# Target_Control_System.net
KiCad netlist of a schematic drawn in Altium Designer
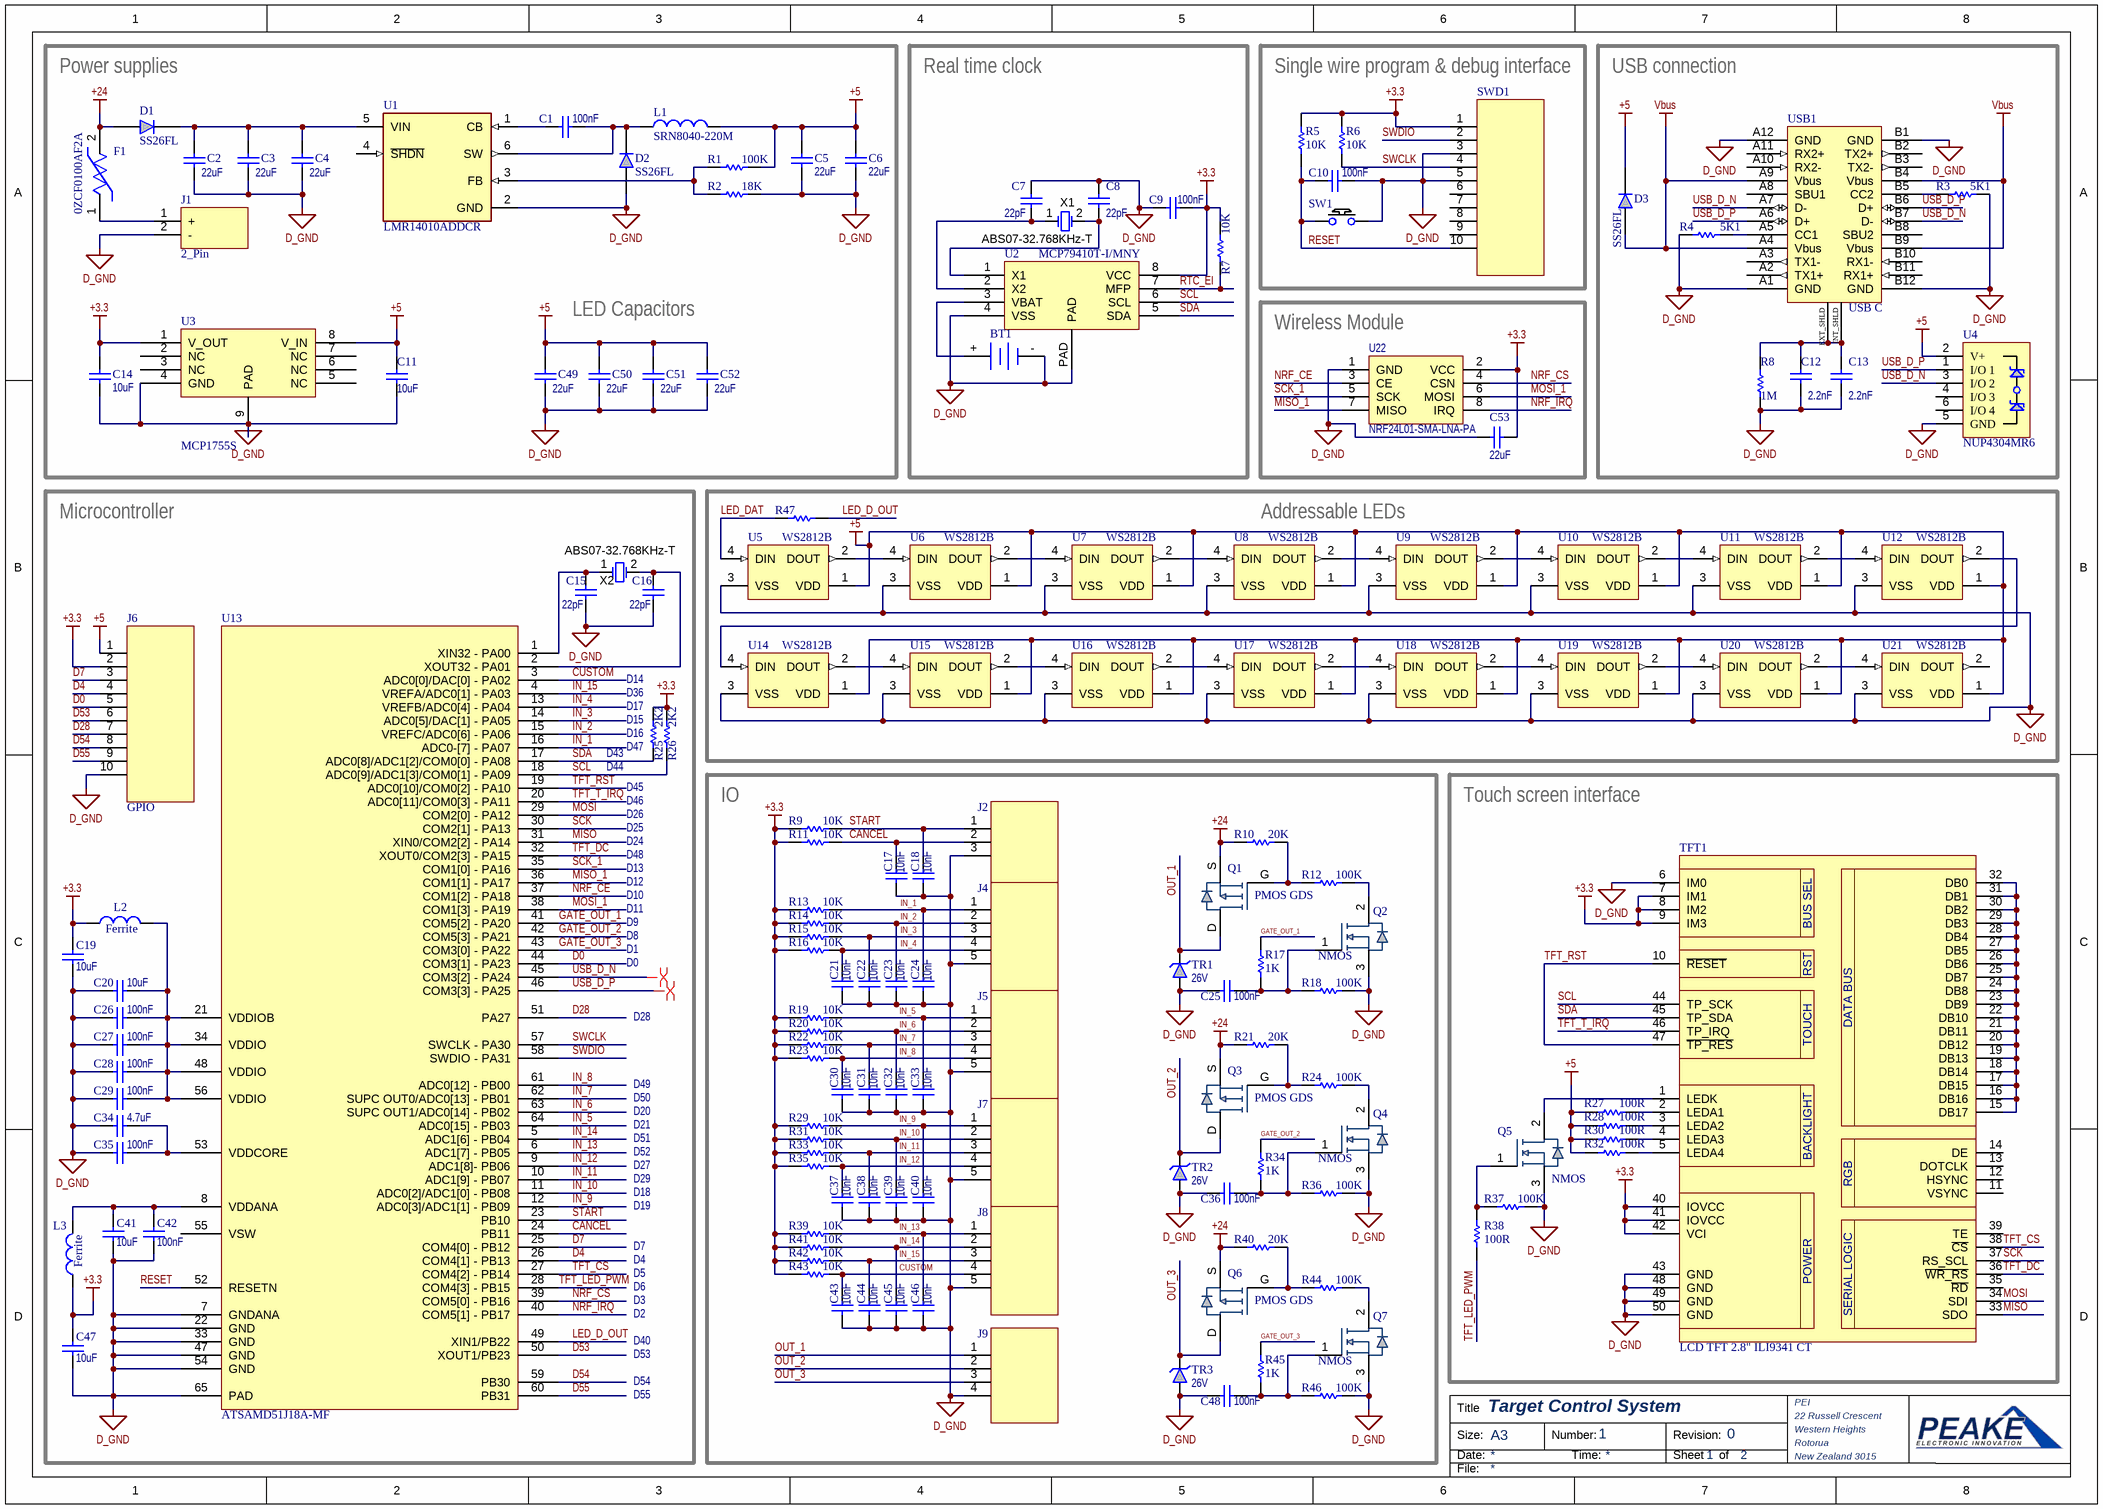
[diagram p0: Target Control System.SchDoc]

(export (version "E")
  (design (tool "Eeschema 10.0.6"))
  (components
    (comp (ref "BT1")
      (value "CR2032 Batt Holder")
      (footprint "CR2032 Batt Holder-Footprint-1")
      (description "SMD CR2032 coin cell holder")
      (libsource (lib "Scion Research") (part "CMP-00042-2"))
    )
    (comp (ref "C1")
      (value "100nF")
      (footprint "0603_CAP")
      (description "SMD Capacitor")
      (fields (field (name "Comment") "Capacitor"))
      (libsource (lib "Scion Research") (part "CMP-019-00005-2"))
    )
    (comp (ref "C2")
      (value "22uF")
      (footprint "0805_CAP")
      (description "SMD Capacitor")
      (fields (field (name "Comment") "Capacitor"))
      (libsource (lib "Scion Research") (part "CMP-019-00005-2"))
    )
    (comp (ref "C3")
      (value "22uF")
      (footprint "0805_CAP")
      (description "SMD Capacitor")
      (fields (field (name "Comment") "Capacitor"))
      (libsource (lib "Scion Research") (part "CMP-019-00005-2"))
    )
    (comp (ref "C4")
      (value "22uF")
      (footprint "0805_CAP")
      (description "SMD Capacitor")
      (fields (field (name "Comment") "Capacitor"))
      (libsource (lib "Scion Research") (part "CMP-019-00005-2"))
    )
    (comp (ref "C5")
      (value "22uF")
      (footprint "0805_CAP")
      (description "SMD Capacitor")
      (fields (field (name "Comment") "Capacitor"))
      (libsource (lib "Scion Research") (part "CMP-019-00005-2"))
    )
    (comp (ref "C6")
      (value "22uF")
      (footprint "0805_CAP")
      (description "SMD Capacitor")
      (fields (field (name "Comment") "Capacitor"))
      (libsource (lib "Scion Research") (part "CMP-019-00005-2"))
    )
    (comp (ref "C7")
      (value "22pF")
      (footprint "0603_CAP")
      (description "SMD Capacitor")
      (fields (field (name "Comment") "Capacitor"))
      (libsource (lib "Scion Research") (part "CMP-019-00005-2"))
    )
    (comp (ref "C8")
      (value "22pF")
      (footprint "0603_CAP")
      (description "SMD Capacitor")
      (fields (field (name "Comment") "Capacitor"))
      (libsource (lib "Scion Research") (part "CMP-019-00005-2"))
    )
    (comp (ref "C9")
      (value "100nF")
      (footprint "0603_CAP")
      (description "SMD Capacitor")
      (fields (field (name "Comment") "Capacitor"))
      (libsource (lib "Scion Research") (part "CMP-019-00005-2"))
    )
    (comp (ref "C10")
      (value "100nF")
      (footprint "0603_CAP")
      (description "SMD Capacitor")
      (fields (field (name "Comment") "Capacitor"))
      (libsource (lib "Scion Research") (part "CMP-019-00005-2"))
    )
    (comp (ref "C11")
      (value "10uF")
      (footprint "0603_CAP")
      (description "SMD Capacitor")
      (fields (field (name "Comment") "Capacitor"))
      (libsource (lib "Scion Research") (part "CMP-019-00005-2"))
    )
    (comp (ref "C12")
      (value "2.2nF")
      (footprint "0603_CAP")
      (description "SMD Capacitor")
      (fields (field (name "Comment") "Capacitor"))
      (libsource (lib "Scion Research") (part "CMP-019-00005-2"))
    )
    (comp (ref "C13")
      (value "2.2nF")
      (footprint "0603_CAP")
      (description "SMD Capacitor")
      (fields (field (name "Comment") "Capacitor"))
      (libsource (lib "Scion Research") (part "CMP-019-00005-2"))
    )
    (comp (ref "C14")
      (value "10uF")
      (footprint "0603_CAP")
      (description "SMD Capacitor")
      (fields (field (name "Comment") "Capacitor"))
      (libsource (lib "Scion Research") (part "CMP-019-00005-2"))
    )
    (comp (ref "C15")
      (value "22pF")
      (footprint "0603_CAP")
      (description "SMD Capacitor")
      (fields (field (name "Comment") "Capacitor"))
      (libsource (lib "Scion Research") (part "CMP-019-00005-2"))
    )
    (comp (ref "C16")
      (value "22pF")
      (footprint "0603_CAP")
      (description "SMD Capacitor")
      (fields (field (name "Comment") "Capacitor"))
      (libsource (lib "Scion Research") (part "CMP-019-00005-2"))
    )
    (comp (ref "C17")
      (value "10nF")
      (footprint "0603_CAP")
      (description "SMD Capacitor")
      (fields (field (name "Comment") "Capacitor"))
      (libsource (lib "Scion Research") (part "CMP-019-00005-2"))
    )
    (comp (ref "C18")
      (value "10nF")
      (footprint "0603_CAP")
      (description "SMD Capacitor")
      (fields (field (name "Comment") "Capacitor"))
      (libsource (lib "Scion Research") (part "CMP-019-00005-2"))
    )
    (comp (ref "C19")
      (value "10uF")
      (footprint "0603_CAP")
      (description "SMD Capacitor")
      (fields (field (name "Comment") "Capacitor"))
      (libsource (lib "Scion Research") (part "CMP-019-00005-2"))
    )
    (comp (ref "C20")
      (value "10uF")
      (footprint "0603_CAP")
      (description "SMD Capacitor")
      (fields (field (name "Comment") "Capacitor"))
      (libsource (lib "Scion Research") (part "CMP-019-00005-2"))
    )
    (comp (ref "C21")
      (value "10nF")
      (footprint "0603_CAP")
      (description "SMD Capacitor")
      (fields (field (name "Comment") "Capacitor"))
      (libsource (lib "Scion Research") (part "CMP-019-00005-2"))
    )
    (comp (ref "C22")
      (value "10nF")
      (footprint "0603_CAP")
      (description "SMD Capacitor")
      (fields (field (name "Comment") "Capacitor"))
      (libsource (lib "Scion Research") (part "CMP-019-00005-2"))
    )
    (comp (ref "C23")
      (value "10nF")
      (footprint "0603_CAP")
      (description "SMD Capacitor")
      (fields (field (name "Comment") "Capacitor"))
      (libsource (lib "Scion Research") (part "CMP-019-00005-2"))
    )
    (comp (ref "C24")
      (value "10nF")
      (footprint "0603_CAP")
      (description "SMD Capacitor")
      (fields (field (name "Comment") "Capacitor"))
      (libsource (lib "Scion Research") (part "CMP-019-00005-2"))
    )
    (comp (ref "C25")
      (value "100nF")
      (footprint "0603_CAP")
      (description "SMD Capacitor")
      (fields (field (name "Comment") "Capacitor"))
      (libsource (lib "Scion Research") (part "CMP-019-00005-2"))
    )
    (comp (ref "C26")
      (value "100nF")
      (footprint "0603_CAP")
      (description "SMD Capacitor")
      (fields (field (name "Comment") "Capacitor"))
      (libsource (lib "Scion Research") (part "CMP-019-00005-2"))
    )
    (comp (ref "C27")
      (value "100nF")
      (footprint "0603_CAP")
      (description "SMD Capacitor")
      (fields (field (name "Comment") "Capacitor"))
      (libsource (lib "Scion Research") (part "CMP-019-00005-2"))
    )
    (comp (ref "C28")
      (value "100nF")
      (footprint "0603_CAP")
      (description "SMD Capacitor")
      (fields (field (name "Comment") "Capacitor"))
      (libsource (lib "Scion Research") (part "CMP-019-00005-2"))
    )
    (comp (ref "C29")
      (value "100nF")
      (footprint "0603_CAP")
      (description "SMD Capacitor")
      (fields (field (name "Comment") "Capacitor"))
      (libsource (lib "Scion Research") (part "CMP-019-00005-2"))
    )
    (comp (ref "C30")
      (value "10nF")
      (footprint "0603_CAP")
      (description "SMD Capacitor")
      (fields (field (name "Comment") "Capacitor"))
      (libsource (lib "Scion Research") (part "CMP-019-00005-2"))
    )
    (comp (ref "C31")
      (value "10nF")
      (footprint "0603_CAP")
      (description "SMD Capacitor")
      (fields (field (name "Comment") "Capacitor"))
      (libsource (lib "Scion Research") (part "CMP-019-00005-2"))
    )
    (comp (ref "C32")
      (value "10nF")
      (footprint "0603_CAP")
      (description "SMD Capacitor")
      (fields (field (name "Comment") "Capacitor"))
      (libsource (lib "Scion Research") (part "CMP-019-00005-2"))
    )
    (comp (ref "C33")
      (value "10nF")
      (footprint "0603_CAP")
      (description "SMD Capacitor")
      (fields (field (name "Comment") "Capacitor"))
      (libsource (lib "Scion Research") (part "CMP-019-00005-2"))
    )
    (comp (ref "C34")
      (value "4.7uF")
      (footprint "0603_CAP")
      (description "SMD Capacitor")
      (fields (field (name "Comment") "Capacitor"))
      (libsource (lib "Scion Research") (part "CMP-019-00005-2"))
    )
    (comp (ref "C35")
      (value "100nF")
      (footprint "0603_CAP")
      (description "SMD Capacitor")
      (fields (field (name "Comment") "Capacitor"))
      (libsource (lib "Scion Research") (part "CMP-019-00005-2"))
    )
    (comp (ref "C36")
      (value "100nF")
      (footprint "0603_CAP")
      (description "SMD Capacitor")
      (fields (field (name "Comment") "Capacitor"))
      (libsource (lib "Scion Research") (part "CMP-019-00005-2"))
    )
    (comp (ref "C37")
      (value "10nF")
      (footprint "0603_CAP")
      (description "SMD Capacitor")
      (fields (field (name "Comment") "Capacitor"))
      (libsource (lib "Scion Research") (part "CMP-019-00005-2"))
    )
    (comp (ref "C38")
      (value "10nF")
      (footprint "0603_CAP")
      (description "SMD Capacitor")
      (fields (field (name "Comment") "Capacitor"))
      (libsource (lib "Scion Research") (part "CMP-019-00005-2"))
    )
    (comp (ref "C39")
      (value "10nF")
      (footprint "0603_CAP")
      (description "SMD Capacitor")
      (fields (field (name "Comment") "Capacitor"))
      (libsource (lib "Scion Research") (part "CMP-019-00005-2"))
    )
    (comp (ref "C40")
      (value "10nF")
      (footprint "0603_CAP")
      (description "SMD Capacitor")
      (fields (field (name "Comment") "Capacitor"))
      (libsource (lib "Scion Research") (part "CMP-019-00005-2"))
    )
    (comp (ref "C41")
      (value "10uF")
      (footprint "0603_CAP")
      (description "SMD Capacitor")
      (fields (field (name "Comment") "Capacitor"))
      (libsource (lib "Scion Research") (part "CMP-019-00005-2"))
    )
    (comp (ref "C42")
      (value "100nF")
      (footprint "0603_CAP")
      (description "SMD Capacitor")
      (fields (field (name "Comment") "Capacitor"))
      (libsource (lib "Scion Research") (part "CMP-019-00005-2"))
    )
    (comp (ref "C43")
      (value "10nF")
      (footprint "0603_CAP")
      (description "SMD Capacitor")
      (fields (field (name "Comment") "Capacitor"))
      (libsource (lib "Scion Research") (part "CMP-019-00005-2"))
    )
    (comp (ref "C44")
      (value "10nF")
      (footprint "0603_CAP")
      (description "SMD Capacitor")
      (fields (field (name "Comment") "Capacitor"))
      (libsource (lib "Scion Research") (part "CMP-019-00005-2"))
    )
    (comp (ref "C45")
      (value "10nF")
      (footprint "0603_CAP")
      (description "SMD Capacitor")
      (fields (field (name "Comment") "Capacitor"))
      (libsource (lib "Scion Research") (part "CMP-019-00005-2"))
    )
    (comp (ref "C46")
      (value "10nF")
      (footprint "0603_CAP")
      (description "SMD Capacitor")
      (fields (field (name "Comment") "Capacitor"))
      (libsource (lib "Scion Research") (part "CMP-019-00005-2"))
    )
    (comp (ref "C47")
      (value "10uF")
      (footprint "0603_CAP")
      (description "SMD Capacitor")
      (fields (field (name "Comment") "Capacitor"))
      (libsource (lib "Scion Research") (part "CMP-019-00005-2"))
    )
    (comp (ref "C48")
      (value "100nF")
      (footprint "0603_CAP")
      (description "SMD Capacitor")
      (fields (field (name "Comment") "Capacitor"))
      (libsource (lib "Scion Research") (part "CMP-019-00005-2"))
    )
    (comp (ref "C49")
      (value "22uF")
      (footprint "0805_CAP")
      (description "SMD Capacitor")
      (fields (field (name "Comment") "Capacitor"))
      (libsource (lib "Scion Research") (part "CMP-019-00005-2"))
    )
    (comp (ref "C50")
      (value "22uF")
      (footprint "0805_CAP")
      (description "SMD Capacitor")
      (fields (field (name "Comment") "Capacitor"))
      (libsource (lib "Scion Research") (part "CMP-019-00005-2"))
    )
    (comp (ref "C51")
      (value "22uF")
      (footprint "0805_CAP")
      (description "SMD Capacitor")
      (fields (field (name "Comment") "Capacitor"))
      (libsource (lib "Scion Research") (part "CMP-019-00005-2"))
    )
    (comp (ref "C52")
      (value "22uF")
      (footprint "0805_CAP")
      (description "SMD Capacitor")
      (fields (field (name "Comment") "Capacitor"))
      (libsource (lib "Scion Research") (part "CMP-019-00005-2"))
    )
    (comp (ref "C53")
      (value "22uF")
      (footprint "0805_CAP")
      (description "SMD Capacitor")
      (fields (field (name "Comment") "Capacitor"))
      (libsource (lib "Scion Research") (part "CMP-019-00005-2"))
    )
    (comp (ref "D1")
      (value "SS26FL")
      (footprint "MCC-SOD123_V")
      (description "ON SEMICONDUCTOR - SS26FL - Schottky Rectifier, 60 V, 2 A, Single, SOD-123F, 2 Pins, 700 mV")
      (libsource (lib "Scion Research") (part "CMP-00026-1"))
    )
    (comp (ref "D2")
      (value "SS26FL")
      (footprint "MCC-SOD123_V")
      (description "ON SEMICONDUCTOR - SS26FL - Schottky Rectifier, 60 V, 2 A, Single, SOD-123F, 2 Pins, 700 mV")
      (libsource (lib "Scion Research") (part "CMP-00026-1"))
    )
    (comp (ref "D3")
      (value "SS26FL")
      (footprint "MCC-SOD123_V")
      (description "ON SEMICONDUCTOR - SS26FL - Schottky Rectifier, 60 V, 2 A, Single, SOD-123F, 2 Pins, 700 mV")
      (libsource (lib "Scion Research") (part "CMP-00026-1"))
    )
    (comp (ref "F1")
      (value "0ZCF0100AF2A")
      (footprint "FP-0ZCF0100AF2A-MFG")
      (description "PTC Resettable Fuse 100A 0.5s 60VDC 0.09 Ohm 2-Pin 2920 T/R")
      (libsource (lib "Scion Research") (part "CMP-00051-1"))
    )
    (comp (ref "J1")
      (value "2_Pin")
      (footprint "2P MOLEX Micro-fit 3.0mm RA SR")
      (description "2 Pin Connector")
      (libsource (lib "Scion Research") (part "CMP-002-00074-8"))
    )
    (comp (ref "J2")
      (value "3_Pin")
      (footprint "3P RA SMD MOLEX Clik-MATE 1.5mm")
      (description "3 Pin Connector")
      (libsource (lib "Scion Research") (part "CMP-002-00075-6"))
    )
    (comp (ref "J4")
      (value "5_Pin")
      (footprint "5P RA SMD MOLEX Clik-MATE 1.5mm")
      (description "5 Pin Connector")
      (libsource (lib "Scion Research") (part "CMP-002-00080-2"))
    )
    (comp (ref "J5")
      (value "5_Pin")
      (footprint "5P RA SMD MOLEX Clik-MATE 1.5mm")
      (description "5 Pin Connector")
      (libsource (lib "Scion Research") (part "CMP-002-00080-2"))
    )
    (comp (ref "J6")
      (value "GPIO")
      (footprint "10P 2.54mm PTH Male Header")
      (description "10 Pin Connector")
      (libsource (lib "Scion Research") (part "CMP-002-00071-2"))
    )
    (comp (ref "J7")
      (value "5_Pin")
      (footprint "5P RA SMD MOLEX Clik-MATE 1.5mm")
      (description "5 Pin Connector")
      (libsource (lib "Scion Research") (part "CMP-002-00080-2"))
    )
    (comp (ref "J8")
      (value "5_Pin")
      (footprint "5P RA SMD MOLEX Clik-MATE 1.5mm")
      (description "5 Pin Connector")
      (libsource (lib "Scion Research") (part "CMP-002-00080-2"))
    )
    (comp (ref "J9")
      (value "4_Pin")
      (footprint "4P MOLEX Micro-fit 3.0mm RA SR")
      (description "4 Pin Connector")
      (libsource (lib "Scion Research") (part "CMP-002-00078-6"))
    )
    (comp (ref "L1")
      (value "SRN8040-220M")
      (footprint "BOUR-SRN8040_V")
      (description "Inductor;  Power;  Semi-Shielded;  Ind 22 uH;  Tol 20%;  Cur-Rtg 2.2 A;  SMT")
      (fields (field (name "TOLERANCE") "20%"))
      (libsource (lib "Scion Research") (part "CMP-006-00022-4"))
    )
    (comp (ref "L2")
      (value "Ferrite")
      (footprint "1806_IND")
      (libsource (lib "Scion Research") (part "CMP-006-00021-1"))
    )
    (comp (ref "L3")
      (value "Ferrite")
      (footprint "1806_IND")
      (libsource (lib "Scion Research") (part "CMP-006-00021-1"))
    )
    (comp (ref "Q1")
      (value "PMOS GDS")
      (footprint "PowerDI 5060-8")
      (description "P Channel MOSFET")
      (libsource (lib "Scion Research") (part "CMP-004-0035-2"))
    )
    (comp (ref "Q2")
      (value "NMOS")
      (footprint "SOT-23")
      (description "N Channel MOSFET")
      (libsource (lib "Scion Research") (part "CMP-004-0025-1"))
    )
    (comp (ref "Q3")
      (value "PMOS GDS")
      (footprint "PowerDI 5060-8")
      (description "P Channel MOSFET")
      (libsource (lib "Scion Research") (part "CMP-004-0035-2"))
    )
    (comp (ref "Q4")
      (value "NMOS")
      (footprint "SOT-23")
      (description "N Channel MOSFET")
      (libsource (lib "Scion Research") (part "CMP-004-0025-1"))
    )
    (comp (ref "Q5")
      (value "NMOS")
      (footprint "SOT-23")
      (description "N Channel MOSFET")
      (libsource (lib "Scion Research") (part "CMP-004-0025-1"))
    )
    (comp (ref "Q6")
      (value "PMOS GDS")
      (footprint "PowerDI 5060-8")
      (description "P Channel MOSFET")
      (libsource (lib "Scion Research") (part "CMP-004-0035-2"))
    )
    (comp (ref "Q7")
      (value "NMOS")
      (footprint "SOT-23")
      (description "N Channel MOSFET")
      (libsource (lib "Scion Research") (part "CMP-004-0025-1"))
    )
    (comp (ref "R1")
      (value "100K")
      (footprint "0603_RES")
      (description "SMD Resistor")
      (fields (field (name "Comment") "Resistor"))
      (libsource (lib "Scion Research") (part "CMP-009-00177-2"))
    )
    (comp (ref "R2")
      (value "18K")
      (footprint "0603_RES")
      (description "SMD Resistor")
      (fields (field (name "Comment") "Resistor"))
      (libsource (lib "Scion Research") (part "CMP-009-00177-2"))
    )
    (comp (ref "R3")
      (value "5K1")
      (footprint "0603_RES")
      (description "SMD Resistor")
      (fields (field (name "Comment") "Resistor"))
      (libsource (lib "Scion Research") (part "CMP-009-00177-2"))
    )
    (comp (ref "R4")
      (value "5K1")
      (footprint "0603_RES")
      (description "SMD Resistor")
      (fields (field (name "Comment") "Resistor"))
      (libsource (lib "Scion Research") (part "CMP-009-00177-2"))
    )
    (comp (ref "R5")
      (value "10K")
      (footprint "0603_RES")
      (description "SMD Resistor")
      (fields (field (name "Comment") "Resistor"))
      (libsource (lib "Scion Research") (part "CMP-009-00177-2"))
    )
    (comp (ref "R6")
      (value "10K")
      (footprint "0603_RES")
      (description "SMD Resistor")
      (fields (field (name "Comment") "Resistor"))
      (libsource (lib "Scion Research") (part "CMP-009-00177-2"))
    )
    (comp (ref "R7")
      (value "10K")
      (footprint "0603_RES")
      (description "SMD Resistor")
      (fields (field (name "Comment") "Resistor"))
      (libsource (lib "Scion Research") (part "CMP-009-00177-2"))
    )
    (comp (ref "R8")
      (value "1M")
      (footprint "0603_RES")
      (description "SMD Resistor")
      (fields (field (name "Comment") "Resistor"))
      (libsource (lib "Scion Research") (part "CMP-009-00177-2"))
    )
    (comp (ref "R9")
      (value "10K")
      (footprint "0603_RES")
      (description "SMD Resistor")
      (fields (field (name "Comment") "Resistor"))
      (libsource (lib "Scion Research") (part "CMP-009-00177-2"))
    )
    (comp (ref "R10")
      (value "20K")
      (footprint "0603_RES")
      (description "SMD Resistor")
      (fields (field (name "Comment") "Resistor"))
      (libsource (lib "Scion Research") (part "CMP-009-00177-2"))
    )
    (comp (ref "R11")
      (value "10K")
      (footprint "0603_RES")
      (description "SMD Resistor")
      (fields (field (name "Comment") "Resistor"))
      (libsource (lib "Scion Research") (part "CMP-009-00177-2"))
    )
    (comp (ref "R12")
      (value "100K")
      (footprint "0603_RES")
      (description "SMD Resistor")
      (fields (field (name "Comment") "Resistor"))
      (libsource (lib "Scion Research") (part "CMP-009-00177-2"))
    )
    (comp (ref "R13")
      (value "10K")
      (footprint "0603_RES")
      (description "SMD Resistor")
      (fields (field (name "Comment") "Resistor"))
      (libsource (lib "Scion Research") (part "CMP-009-00177-2"))
    )
    (comp (ref "R14")
      (value "10K")
      (footprint "0603_RES")
      (description "SMD Resistor")
      (fields (field (name "Comment") "Resistor"))
      (libsource (lib "Scion Research") (part "CMP-009-00177-2"))
    )
    (comp (ref "R15")
      (value "10K")
      (footprint "0603_RES")
      (description "SMD Resistor")
      (fields (field (name "Comment") "Resistor"))
      (libsource (lib "Scion Research") (part "CMP-009-00177-2"))
    )
    (comp (ref "R16")
      (value "10K")
      (footprint "0603_RES")
      (description "SMD Resistor")
      (fields (field (name "Comment") "Resistor"))
      (libsource (lib "Scion Research") (part "CMP-009-00177-2"))
    )
    (comp (ref "R17")
      (value "1K")
      (footprint "0603_RES")
      (description "SMD Resistor")
      (fields (field (name "Comment") "Resistor"))
      (libsource (lib "Scion Research") (part "CMP-009-00177-2"))
    )
    (comp (ref "R18")
      (value "100K")
      (footprint "0603_RES")
      (description "SMD Resistor")
      (fields (field (name "Comment") "Resistor"))
      (libsource (lib "Scion Research") (part "CMP-009-00177-2"))
    )
    (comp (ref "R19")
      (value "10K")
      (footprint "0603_RES")
      (description "SMD Resistor")
      (fields (field (name "Comment") "Resistor"))
      (libsource (lib "Scion Research") (part "CMP-009-00177-2"))
    )
    (comp (ref "R20")
      (value "10K")
      (footprint "0603_RES")
      (description "SMD Resistor")
      (fields (field (name "Comment") "Resistor"))
      (libsource (lib "Scion Research") (part "CMP-009-00177-2"))
    )
    (comp (ref "R21")
      (value "20K")
      (footprint "0603_RES")
      (description "SMD Resistor")
      (fields (field (name "Comment") "Resistor"))
      (libsource (lib "Scion Research") (part "CMP-009-00177-2"))
    )
    (comp (ref "R22")
      (value "10K")
      (footprint "0603_RES")
      (description "SMD Resistor")
      (fields (field (name "Comment") "Resistor"))
      (libsource (lib "Scion Research") (part "CMP-009-00177-2"))
    )
    (comp (ref "R23")
      (value "10K")
      (footprint "0603_RES")
      (description "SMD Resistor")
      (fields (field (name "Comment") "Resistor"))
      (libsource (lib "Scion Research") (part "CMP-009-00177-2"))
    )
    (comp (ref "R24")
      (value "100K")
      (footprint "0603_RES")
      (description "SMD Resistor")
      (fields (field (name "Comment") "Resistor"))
      (libsource (lib "Scion Research") (part "CMP-009-00177-2"))
    )
    (comp (ref "R25")
      (value "2K2")
      (footprint "0603_RES")
      (description "SMD Resistor")
      (fields (field (name "Comment") "Resistor"))
      (libsource (lib "Scion Research") (part "CMP-009-00177-2"))
    )
    (comp (ref "R26")
      (value "2K2")
      (footprint "0603_RES")
      (description "SMD Resistor")
      (fields (field (name "Comment") "Resistor"))
      (libsource (lib "Scion Research") (part "CMP-009-00177-2"))
    )
    (comp (ref "R27")
      (value "100R")
      (footprint "0603_RES")
      (description "SMD Resistor")
      (fields (field (name "Comment") "Resistor"))
      (libsource (lib "Scion Research") (part "CMP-009-00177-2"))
    )
    (comp (ref "R28")
      (value "100R")
      (footprint "0603_RES")
      (description "SMD Resistor")
      (fields (field (name "Comment") "Resistor"))
      (libsource (lib "Scion Research") (part "CMP-009-00177-2"))
    )
    (comp (ref "R29")
      (value "10K")
      (footprint "0603_RES")
      (description "SMD Resistor")
      (fields (field (name "Comment") "Resistor"))
      (libsource (lib "Scion Research") (part "CMP-009-00177-2"))
    )
    (comp (ref "R30")
      (value "100R")
      (footprint "0603_RES")
      (description "SMD Resistor")
      (fields (field (name "Comment") "Resistor"))
      (libsource (lib "Scion Research") (part "CMP-009-00177-2"))
    )
    (comp (ref "R31")
      (value "10K")
      (footprint "0603_RES")
      (description "SMD Resistor")
      (fields (field (name "Comment") "Resistor"))
      (libsource (lib "Scion Research") (part "CMP-009-00177-2"))
    )
    (comp (ref "R32")
      (value "100R")
      (footprint "0603_RES")
      (description "SMD Resistor")
      (fields (field (name "Comment") "Resistor"))
      (libsource (lib "Scion Research") (part "CMP-009-00177-2"))
    )
    (comp (ref "R33")
      (value "10K")
      (footprint "0603_RES")
      (description "SMD Resistor")
      (fields (field (name "Comment") "Resistor"))
      (libsource (lib "Scion Research") (part "CMP-009-00177-2"))
    )
    (comp (ref "R34")
      (value "1K")
      (footprint "0603_RES")
      (description "SMD Resistor")
      (fields (field (name "Comment") "Resistor"))
      (libsource (lib "Scion Research") (part "CMP-009-00177-2"))
    )
    (comp (ref "R35")
      (value "10K")
      (footprint "0603_RES")
      (description "SMD Resistor")
      (fields (field (name "Comment") "Resistor"))
      (libsource (lib "Scion Research") (part "CMP-009-00177-2"))
    )
    (comp (ref "R36")
      (value "100K")
      (footprint "0603_RES")
      (description "SMD Resistor")
      (fields (field (name "Comment") "Resistor"))
      (libsource (lib "Scion Research") (part "CMP-009-00177-2"))
    )
    (comp (ref "R37")
      (value "100K")
      (footprint "0603_RES")
      (description "SMD Resistor")
      (fields (field (name "Comment") "Resistor"))
      (libsource (lib "Scion Research") (part "CMP-009-00177-2"))
    )
    (comp (ref "R38")
      (value "100R")
      (footprint "0603_RES")
      (description "SMD Resistor")
      (fields (field (name "Comment") "Resistor"))
      (libsource (lib "Scion Research") (part "CMP-009-00177-2"))
    )
    (comp (ref "R39")
      (value "10K")
      (footprint "0603_RES")
      (description "SMD Resistor")
      (fields (field (name "Comment") "Resistor"))
      (libsource (lib "Scion Research") (part "CMP-009-00177-2"))
    )
    (comp (ref "R40")
      (value "20K")
      (footprint "0603_RES")
      (description "SMD Resistor")
      (fields (field (name "Comment") "Resistor"))
      (libsource (lib "Scion Research") (part "CMP-009-00177-2"))
    )
    (comp (ref "R41")
      (value "10K")
      (footprint "0603_RES")
      (description "SMD Resistor")
      (fields (field (name "Comment") "Resistor"))
      (libsource (lib "Scion Research") (part "CMP-009-00177-2"))
    )
    (comp (ref "R42")
      (value "10K")
      (footprint "0603_RES")
      (description "SMD Resistor")
      (fields (field (name "Comment") "Resistor"))
      (libsource (lib "Scion Research") (part "CMP-009-00177-2"))
    )
    (comp (ref "R43")
      (value "10K")
      (footprint "0603_RES")
      (description "SMD Resistor")
      (fields (field (name "Comment") "Resistor"))
      (libsource (lib "Scion Research") (part "CMP-009-00177-2"))
    )
    (comp (ref "R44")
      (value "100K")
      (footprint "0603_RES")
      (description "SMD Resistor")
      (fields (field (name "Comment") "Resistor"))
      (libsource (lib "Scion Research") (part "CMP-009-00177-2"))
    )
    (comp (ref "R45")
      (value "1K")
      (footprint "0603_RES")
      (description "SMD Resistor")
      (fields (field (name "Comment") "Resistor"))
      (libsource (lib "Scion Research") (part "CMP-009-00177-2"))
    )
    (comp (ref "R46")
      (value "100K")
      (footprint "0603_RES")
      (description "SMD Resistor")
      (fields (field (name "Comment") "Resistor"))
      (libsource (lib "Scion Research") (part "CMP-009-00177-2"))
    )
    (comp (ref "R47")
      (value "Resistor")
      (footprint "0603_RES")
      (description "SMD Resistor")
      (libsource (lib "Scion Research") (part "CMP-009-00177-2"))
    )
    (comp (ref "SW1")
      (value "Button")
      (footprint "EVQP7A_SW")
      (description "Momentary push button")
      (libsource (lib "Scion Research") (part "CMP-011-00013-6"))
    )
    (comp (ref "SWD1")
      (value "10_Pin")
      (footprint "DIP10_1.27_M_SMD")
      (description "10 Pin Connector")
      (libsource (lib "Scion Research") (part "CMP-002-00071-2"))
    )
    (comp (ref "TFT1")
      (value "LCD TFT 2.8\" ILI9341 CT")
      (footprint "LCD TFT 2.8\" ILI9341 CT-Folded-OFFSET")
      (libsource (lib "Scion Research") (part "CMP-00028-6"))
    )
    (comp (ref "TR1")
      (value "Transil")
      (footprint "SMBJ")
      (description "Transient Voltage Suppressor")
      (fields (field (name "RATED VOLTAGE") "26V"))
      (libsource (lib "Scion Research") (part "CMP-004-0042-1"))
    )
    (comp (ref "TR2")
      (value "Transil")
      (footprint "SMBJ")
      (description "Transient Voltage Suppressor")
      (fields (field (name "RATED VOLTAGE") "26V"))
      (libsource (lib "Scion Research") (part "CMP-004-0042-1"))
    )
    (comp (ref "TR3")
      (value "Transil")
      (footprint "SMBJ")
      (description "Transient Voltage Suppressor")
      (fields (field (name "RATED VOLTAGE") "26V"))
      (libsource (lib "Scion Research") (part "CMP-004-0042-1"))
    )
    (comp (ref "U1")
      (value "LMR14010ADDCR")
      (footprint "FP-DDC0006A-IPC_A")
      (description "LV2843")
      (libsource (lib "Scion Research") (part "CMP-00007-1"))
    )
    (comp (ref "U2")
      (value "MCP79410T-I/MNY")
      (footprint "MCP79410T-I_MNY-Footprint-1")
      (description "Real Time Clock Serial 64byte Clock/Calendar/Alarm/Battery Backup Automotive 8-Pin TDFN EP T/R")
      (libsource (lib "Scion Research") (part "CMP-00046-1"))
    )
    (comp (ref "U3")
      (value "MCP1755S")
      (footprint "8P 2x3 DFN")
      (description "LDO Linear Voltage Regulator")
      (libsource (lib "Scion Research") (part "CMP-004-0021-1"))
    )
    (comp (ref "U4")
      (value "NUP4304MR6")
      (footprint "TSOP-6")
      (description "ESD Protection Doide Array")
      (libsource (lib "Scion Research") (part "CMP-004-0028-1"))
    )
    (comp (ref "U5")
      (value "WS2812B")
      (footprint "ADAI-WS2812B_V")
      (fields (field (name "MANUFACTURER") "Adafruit Industries"))
      (libsource (lib "Scion Research") (part "CMP-007-00035-3"))
    )
    (comp (ref "U6")
      (value "WS2812B")
      (footprint "ADAI-WS2812B_V")
      (fields (field (name "MANUFACTURER") "Adafruit Industries"))
      (libsource (lib "Scion Research") (part "CMP-007-00035-3"))
    )
    (comp (ref "U7")
      (value "WS2812B")
      (footprint "ADAI-WS2812B_V")
      (fields (field (name "MANUFACTURER") "Adafruit Industries"))
      (libsource (lib "Scion Research") (part "CMP-007-00035-3"))
    )
    (comp (ref "U8")
      (value "WS2812B")
      (footprint "ADAI-WS2812B_V")
      (fields (field (name "MANUFACTURER") "Adafruit Industries"))
      (libsource (lib "Scion Research") (part "CMP-007-00035-3"))
    )
    (comp (ref "U9")
      (value "WS2812B")
      (footprint "ADAI-WS2812B_V")
      (fields (field (name "MANUFACTURER") "Adafruit Industries"))
      (libsource (lib "Scion Research") (part "CMP-007-00035-3"))
    )
    (comp (ref "U10")
      (value "WS2812B")
      (footprint "ADAI-WS2812B_V")
      (fields (field (name "MANUFACTURER") "Adafruit Industries"))
      (libsource (lib "Scion Research") (part "CMP-007-00035-3"))
    )
    (comp (ref "U11")
      (value "WS2812B")
      (footprint "ADAI-WS2812B_V")
      (fields (field (name "MANUFACTURER") "Adafruit Industries"))
      (libsource (lib "Scion Research") (part "CMP-007-00035-3"))
    )
    (comp (ref "U12")
      (value "WS2812B")
      (footprint "ADAI-WS2812B_V")
      (fields (field (name "MANUFACTURER") "Adafruit Industries"))
      (libsource (lib "Scion Research") (part "CMP-007-00035-3"))
    )
    (comp (ref "U13")
      (value "ATSAMD51J18A-MF")
      (footprint "64M2 65P 9x9 VQFN ATSAME51J")
      (description "MCU 32-Bit ARM Cortex-M4F RISC 256KB Flash 1.71V to 3.63V 64-Pin QFN Tray")
      (libsource (lib "Scion Research") (part "CMP-00048-1"))
    )
    (comp (ref "U14")
      (value "WS2812B")
      (footprint "ADAI-WS2812B_V")
      (fields (field (name "MANUFACTURER") "Adafruit Industries"))
      (libsource (lib "Scion Research") (part "CMP-007-00035-3"))
    )
    (comp (ref "U15")
      (value "WS2812B")
      (footprint "ADAI-WS2812B_V")
      (fields (field (name "MANUFACTURER") "Adafruit Industries"))
      (libsource (lib "Scion Research") (part "CMP-007-00035-3"))
    )
    (comp (ref "U16")
      (value "WS2812B")
      (footprint "ADAI-WS2812B_V")
      (fields (field (name "MANUFACTURER") "Adafruit Industries"))
      (libsource (lib "Scion Research") (part "CMP-007-00035-3"))
    )
    (comp (ref "U17")
      (value "WS2812B")
      (footprint "ADAI-WS2812B_V")
      (fields (field (name "MANUFACTURER") "Adafruit Industries"))
      (libsource (lib "Scion Research") (part "CMP-007-00035-3"))
    )
    (comp (ref "U18")
      (value "WS2812B")
      (footprint "ADAI-WS2812B_V")
      (fields (field (name "MANUFACTURER") "Adafruit Industries"))
      (libsource (lib "Scion Research") (part "CMP-007-00035-3"))
    )
    (comp (ref "U19")
      (value "WS2812B")
      (footprint "ADAI-WS2812B_V")
      (fields (field (name "MANUFACTURER") "Adafruit Industries"))
      (libsource (lib "Scion Research") (part "CMP-007-00035-3"))
    )
    (comp (ref "U20")
      (value "WS2812B")
      (footprint "ADAI-WS2812B_V")
      (fields (field (name "MANUFACTURER") "Adafruit Industries"))
      (libsource (lib "Scion Research") (part "CMP-007-00035-3"))
    )
    (comp (ref "U21")
      (value "WS2812B")
      (footprint "ADAI-WS2812B_V")
      (fields (field (name "MANUFACTURER") "Adafruit Industries"))
      (libsource (lib "Scion Research") (part "CMP-007-00035-3"))
    )
    (comp (ref "U22")
      (value "NRF24L01-SMA-LNA-PA")
      (footprint "NRF24L01-SMA-LNA-PA-Footprint-1")
      (description "NRF 2.4GHz wireless transciever module")
      (libsource (lib "altium-import") (part "root_0_NRF24L01-SMA-LNA-PA-Symbol-1_"))
    )
    (comp (ref "USB1")
      (value "USB C")
      (footprint "12401598E4#2A")
      (description "Vertical or RA Type C Usb Connector Rohs Compliant: Yes")
      (libsource (lib "Scion Research") (part "CMP-00005-5"))
    )
    (comp (ref "X1")
      (value "ABS07-32.768KHz-T")
      (footprint "ABRA-ABS07-2_V")
      (fields (field (name "TOLERANCE") "20ppm") (field (name "MANUFACTURER") "Abracon"))
      (libsource (lib "Scion Research") (part "CMP-003-00022-1"))
    )
    (comp (ref "X2")
      (value "ABS07-32.768KHz-T")
      (footprint "ABRA-ABS07-2_V")
      (fields (field (name "TOLERANCE") "20ppm") (field (name "MANUFACTURER") "Abracon"))
      (libsource (lib "Scion Research") (part "CMP-003-00022-1"))
    )
  )
  (nets
    (net (code "1") (name "+3.3") (class "Default")
      (node (ref "C14") (pin "2") (pinfunction "2_2") (pintype "passive"))
      (node (ref "C19") (pin "1") (pinfunction "1_1") (pintype "passive"))
      (node (ref "C47") (pin "1") (pinfunction "1_1") (pintype "passive"))
      (node (ref "C53") (pin "1") (pinfunction "1_1") (pintype "passive"))
      (node (ref "C9") (pin "1") (pinfunction "1_1") (pintype "passive"))
      (node (ref "J6") (pin "2") (pinfunction "2_2") (pintype "passive"))
      (node (ref "L2") (pin "1") (pinfunction "1_1") (pintype "passive"))
      (node (ref "L3") (pin "1") (pinfunction "1_1") (pintype "passive"))
      (node (ref "R11") (pin "2") (pinfunction "2_2") (pintype "passive"))
      (node (ref "R13") (pin "2") (pinfunction "2_2") (pintype "passive"))
      (node (ref "R14") (pin "2") (pinfunction "2_2") (pintype "passive"))
      (node (ref "R15") (pin "2") (pinfunction "2_2") (pintype "passive"))
      (node (ref "R16") (pin "2") (pinfunction "2_2") (pintype "passive"))
      (node (ref "R19") (pin "2") (pinfunction "2_2") (pintype "passive"))
      (node (ref "R20") (pin "2") (pinfunction "2_2") (pintype "passive"))
      (node (ref "R22") (pin "2") (pinfunction "2_2") (pintype "passive"))
      (node (ref "R23") (pin "2") (pinfunction "2_2") (pintype "passive"))
      (node (ref "R25") (pin "2") (pinfunction "2_2") (pintype "passive"))
      (node (ref "R26") (pin "2") (pinfunction "2_2") (pintype "passive"))
      (node (ref "R29") (pin "2") (pinfunction "2_2") (pintype "passive"))
      (node (ref "R31") (pin "2") (pinfunction "2_2") (pintype "passive"))
      (node (ref "R33") (pin "2") (pinfunction "2_2") (pintype "passive"))
      (node (ref "R35") (pin "2") (pinfunction "2_2") (pintype "passive"))
      (node (ref "R39") (pin "2") (pinfunction "2_2") (pintype "passive"))
      (node (ref "R41") (pin "2") (pinfunction "2_2") (pintype "passive"))
      (node (ref "R42") (pin "2") (pinfunction "2_2") (pintype "passive"))
      (node (ref "R43") (pin "2") (pinfunction "2_2") (pintype "passive"))
      (node (ref "R5") (pin "2") (pinfunction "2_2") (pintype "passive"))
      (node (ref "R6") (pin "2") (pinfunction "2_2") (pintype "passive"))
      (node (ref "R7") (pin "2") (pinfunction "2_2") (pintype "passive"))
      (node (ref "R9") (pin "2") (pinfunction "2_2") (pintype "passive"))
      (node (ref "SWD1") (pin "1") (pinfunction "1_1") (pintype "passive"))
      (node (ref "TFT1") (pin "40") (pinfunction "IOVCC_40") (pintype "passive"))
      (node (ref "TFT1") (pin "41") (pinfunction "IOVCC_41") (pintype "passive"))
      (node (ref "TFT1") (pin "42") (pinfunction "VCI_42") (pintype "passive"))
      (node (ref "TFT1") (pin "7") (pinfunction "IM1_7") (pintype "passive"))
      (node (ref "TFT1") (pin "8") (pinfunction "IM2_8") (pintype "passive"))
      (node (ref "TFT1") (pin "9") (pinfunction "IM3_9") (pintype "passive"))
      (node (ref "U2") (pin "8") (pinfunction "VCC_8") (pintype "passive"))
      (node (ref "U22") (pin "2") (pinfunction "VCC_2") (pintype "passive"))
      (node (ref "U3") (pin "1") (pinfunction "V_OUT_1") (pintype "power_in"))
    )
    (net (code "2") (name "+5") (class "Default")
      (node (ref "C11") (pin "2") (pinfunction "2_2") (pintype "passive"))
      (node (ref "C49") (pin "2") (pinfunction "2_2") (pintype "passive"))
      (node (ref "C5") (pin "2") (pinfunction "2_2") (pintype "passive"))
      (node (ref "C50") (pin "2") (pinfunction "2_2") (pintype "passive"))
      (node (ref "C51") (pin "2") (pinfunction "2_2") (pintype "passive"))
      (node (ref "C52") (pin "2") (pinfunction "2_2") (pintype "passive"))
      (node (ref "C6") (pin "2") (pinfunction "2_2") (pintype "passive"))
      (node (ref "D3") (pin "2") (pinfunction "K_2") (pintype "passive"))
      (node (ref "J6") (pin "1") (pinfunction "1_1") (pintype "passive"))
      (node (ref "L1") (pin "2") (pinfunction "2_2") (pintype "passive"))
      (node (ref "R1") (pin "1") (pinfunction "1_1") (pintype "passive"))
      (node (ref "R27") (pin "2") (pinfunction "2_2") (pintype "passive"))
      (node (ref "R28") (pin "2") (pinfunction "2_2") (pintype "passive"))
      (node (ref "R30") (pin "2") (pinfunction "2_2") (pintype "passive"))
      (node (ref "R32") (pin "2") (pinfunction "2_2") (pintype "passive"))
      (node (ref "U10") (pin "1") (pinfunction "VDD_1") (pintype "power_in"))
      (node (ref "U11") (pin "1") (pinfunction "VDD_1") (pintype "power_in"))
      (node (ref "U12") (pin "1") (pinfunction "VDD_1") (pintype "power_in"))
      (node (ref "U14") (pin "1") (pinfunction "VDD_1") (pintype "power_in"))
      (node (ref "U15") (pin "1") (pinfunction "VDD_1") (pintype "power_in"))
      (node (ref "U16") (pin "1") (pinfunction "VDD_1") (pintype "power_in"))
      (node (ref "U17") (pin "1") (pinfunction "VDD_1") (pintype "power_in"))
      (node (ref "U18") (pin "1") (pinfunction "VDD_1") (pintype "power_in"))
      (node (ref "U19") (pin "1") (pinfunction "VDD_1") (pintype "power_in"))
      (node (ref "U20") (pin "1") (pinfunction "VDD_1") (pintype "power_in"))
      (node (ref "U21") (pin "1") (pinfunction "VDD_1") (pintype "power_in"))
      (node (ref "U3") (pin "8") (pinfunction "V_IN_8") (pintype "power_in"))
      (node (ref "U4") (pin "2") (pinfunction "V+_2") (pintype "power_in"))
      (node (ref "U5") (pin "1") (pinfunction "VDD_1") (pintype "power_in"))
      (node (ref "U6") (pin "1") (pinfunction "VDD_1") (pintype "power_in"))
      (node (ref "U7") (pin "1") (pinfunction "VDD_1") (pintype "power_in"))
      (node (ref "U8") (pin "1") (pinfunction "VDD_1") (pintype "power_in"))
      (node (ref "U9") (pin "1") (pinfunction "VDD_1") (pintype "power_in"))
    )
    (net (code "3") (name "+24") (class "Default")
      (node (ref "D1") (pin "1") (pinfunction "A_1") (pintype "passive"))
      (node (ref "F1") (pin "2") (pinfunction "2_2") (pintype "passive"))
      (node (ref "Q1") (pin "S") (pinfunction "S_S") (pintype "passive"))
      (node (ref "Q3") (pin "S") (pinfunction "S_S") (pintype "passive"))
      (node (ref "Q6") (pin "S") (pinfunction "S_S") (pintype "passive"))
      (node (ref "R10") (pin "2") (pinfunction "2_2") (pintype "passive"))
      (node (ref "R21") (pin "2") (pinfunction "2_2") (pintype "passive"))
      (node (ref "R40") (pin "2") (pinfunction "2_2") (pintype "passive"))
    )
    (net (code "4") (name "/CANCEL") (class "Default")
      (node (ref "C17") (pin "1") (pinfunction "1_1") (pintype "passive"))
      (node (ref "J2") (pin "2") (pinfunction "2_2") (pintype "passive"))
      (node (ref "R11") (pin "1") (pinfunction "1_1") (pintype "passive"))
      (node (ref "U13") (pin "24") (pinfunction "PB11_24") (pintype "passive"))
    )
    (net (code "5") (name "/CUSTOM") (class "Default")
      (node (ref "C43") (pin "1") (pinfunction "1_1") (pintype "passive"))
      (node (ref "J8") (pin "4") (pinfunction "4_4") (pintype "passive"))
      (node (ref "R43") (pin "1") (pinfunction "1_1") (pintype "passive"))
      (node (ref "U13") (pin "3") (pinfunction "ADC0[0]/DAC[0]_-_PA02_3") (pintype "passive"))
    )
    (net (code "6") (name "/D0") (class "Default")
      (node (ref "J6") (pin "5") (pinfunction "5_5") (pintype "passive"))
      (node (ref "U13") (pin "44") (pinfunction "COM3[1]_-_PA23_44") (pintype "passive"))
    )
    (net (code "7") (name "/D4") (class "Default")
      (node (ref "J6") (pin "4") (pinfunction "4_4") (pintype "passive"))
      (node (ref "U13") (pin "26") (pinfunction "COM4[1]_-_PB13_26") (pintype "passive"))
    )
    (net (code "8") (name "/D7") (class "Default")
      (node (ref "J6") (pin "3") (pinfunction "3_3") (pintype "passive"))
      (node (ref "U13") (pin "25") (pinfunction "COM4[0]_-_PB12_25") (pintype "passive"))
    )
    (net (code "9") (name "/D28") (class "Default")
      (node (ref "J6") (pin "7") (pinfunction "7_7") (pintype "passive"))
      (node (ref "U13") (pin "51") (pinfunction "PA27_51") (pintype "passive"))
    )
    (net (code "10") (name "/D53") (class "Default")
      (node (ref "J6") (pin "6") (pinfunction "6_6") (pintype "passive"))
      (node (ref "U13") (pin "50") (pinfunction "XOUT1/PB23_50") (pintype "passive"))
    )
    (net (code "11") (name "/D54") (class "Default")
      (node (ref "J6") (pin "8") (pinfunction "8_8") (pintype "passive"))
      (node (ref "U13") (pin "59") (pinfunction "PB30_59") (pintype "passive"))
    )
    (net (code "12") (name "/D55") (class "Default")
      (node (ref "J6") (pin "9") (pinfunction "9_9") (pintype "passive"))
      (node (ref "U13") (pin "60") (pinfunction "PB31_60") (pintype "passive"))
    )
    (net (code "13") (name "/GATE_OUT_1") (class "Default")
      (node (ref "R17") (pin "1") (pinfunction "1_1") (pintype "passive"))
      (node (ref "U13") (pin "41") (pinfunction "COM5[2]_-_PA20_41") (pintype "passive"))
    )
    (net (code "14") (name "/GATE_OUT_2") (class "Default")
      (node (ref "R34") (pin "1") (pinfunction "1_1") (pintype "passive"))
      (node (ref "U13") (pin "42") (pinfunction "COM5[3]_-_PA21_42") (pintype "passive"))
    )
    (net (code "15") (name "/GATE_OUT_3") (class "Default")
      (node (ref "R45") (pin "1") (pinfunction "1_1") (pintype "passive"))
      (node (ref "U13") (pin "43") (pinfunction "COM3[0]_-_PA22_43") (pintype "passive"))
    )
    (net (code "16") (name "/IN_1") (class "Default")
      (node (ref "C24") (pin "1") (pinfunction "1_1") (pintype "passive"))
      (node (ref "J4") (pin "1") (pinfunction "1_1") (pintype "passive"))
      (node (ref "R13") (pin "1") (pinfunction "1_1") (pintype "passive"))
      (node (ref "U13") (pin "16") (pinfunction "ADC0-[7]_-_PA07_16") (pintype "passive"))
    )
    (net (code "17") (name "/IN_2") (class "Default")
      (node (ref "C23") (pin "1") (pinfunction "1_1") (pintype "passive"))
      (node (ref "J4") (pin "2") (pinfunction "2_2") (pintype "passive"))
      (node (ref "R14") (pin "1") (pinfunction "1_1") (pintype "passive"))
      (node (ref "U13") (pin "15") (pinfunction "VREFC/ADC0[6]_-_PA06_15") (pintype "passive"))
    )
    (net (code "18") (name "/IN_3") (class "Default")
      (node (ref "C22") (pin "1") (pinfunction "1_1") (pintype "passive"))
      (node (ref "J4") (pin "3") (pinfunction "3_3") (pintype "passive"))
      (node (ref "R15") (pin "1") (pinfunction "1_1") (pintype "passive"))
      (node (ref "U13") (pin "14") (pinfunction "ADC0[5]/DAC[1]_-_PA05_14") (pintype "passive"))
    )
    (net (code "19") (name "/IN_4") (class "Default")
      (node (ref "C21") (pin "1") (pinfunction "1_1") (pintype "passive"))
      (node (ref "J4") (pin "4") (pinfunction "4_4") (pintype "passive"))
      (node (ref "R16") (pin "1") (pinfunction "1_1") (pintype "passive"))
      (node (ref "U13") (pin "13") (pinfunction "VREFB/ADC0[4]_-_PA04_13") (pintype "passive"))
    )
    (net (code "20") (name "/IN_5") (class "Default")
      (node (ref "C33") (pin "1") (pinfunction "1_1") (pintype "passive"))
      (node (ref "J5") (pin "1") (pinfunction "1_1") (pintype "passive"))
      (node (ref "R19") (pin "1") (pinfunction "1_1") (pintype "passive"))
      (node (ref "U13") (pin "64") (pinfunction "ADC0[15]_-_PB03_64") (pintype "passive"))
    )
    (net (code "21") (name "/IN_6") (class "Default")
      (node (ref "C32") (pin "1") (pinfunction "1_1") (pintype "passive"))
      (node (ref "J5") (pin "2") (pinfunction "2_2") (pintype "passive"))
      (node (ref "R20") (pin "1") (pinfunction "1_1") (pintype "passive"))
      (node (ref "U13") (pin "63") (pinfunction "SUPC_OUT1/ADC0[14]_-_PB02_63") (pintype "passive"))
    )
    (net (code "22") (name "/IN_7") (class "Default")
      (node (ref "C31") (pin "1") (pinfunction "1_1") (pintype "passive"))
      (node (ref "J5") (pin "3") (pinfunction "3_3") (pintype "passive"))
      (node (ref "R22") (pin "1") (pinfunction "1_1") (pintype "passive"))
      (node (ref "U13") (pin "62") (pinfunction "SUPC_OUT0/ADC0[13]_-_PB01_62") (pintype "passive"))
    )
    (net (code "23") (name "/IN_8") (class "Default")
      (node (ref "C30") (pin "1") (pinfunction "1_1") (pintype "passive"))
      (node (ref "J5") (pin "4") (pinfunction "4_4") (pintype "passive"))
      (node (ref "R23") (pin "1") (pinfunction "1_1") (pintype "passive"))
      (node (ref "U13") (pin "61") (pinfunction "ADC0[12]_-_PB00_61") (pintype "passive"))
    )
    (net (code "24") (name "/IN_9") (class "Default")
      (node (ref "C40") (pin "1") (pinfunction "1_1") (pintype "passive"))
      (node (ref "J7") (pin "1") (pinfunction "1_1") (pintype "passive"))
      (node (ref "R29") (pin "1") (pinfunction "1_1") (pintype "passive"))
      (node (ref "U13") (pin "12") (pinfunction "ADC0[3]/ADC1[1]_-_PB09_12") (pintype "passive"))
    )
    (net (code "25") (name "/IN_10") (class "Default")
      (node (ref "C39") (pin "1") (pinfunction "1_1") (pintype "passive"))
      (node (ref "J7") (pin "2") (pinfunction "2_2") (pintype "passive"))
      (node (ref "R31") (pin "1") (pinfunction "1_1") (pintype "passive"))
      (node (ref "U13") (pin "11") (pinfunction "ADC0[2]/ADC1[0]_-_PB08_11") (pintype "passive"))
    )
    (net (code "26") (name "/IN_11") (class "Default")
      (node (ref "C38") (pin "1") (pinfunction "1_1") (pintype "passive"))
      (node (ref "J7") (pin "3") (pinfunction "3_3") (pintype "passive"))
      (node (ref "R33") (pin "1") (pinfunction "1_1") (pintype "passive"))
      (node (ref "U13") (pin "10") (pinfunction "ADC1[9]_-_PB07_10") (pintype "passive"))
    )
    (net (code "27") (name "/IN_12") (class "Default")
      (node (ref "C37") (pin "1") (pinfunction "1_1") (pintype "passive"))
      (node (ref "J7") (pin "4") (pinfunction "4_4") (pintype "passive"))
      (node (ref "R35") (pin "1") (pinfunction "1_1") (pintype "passive"))
      (node (ref "U13") (pin "9") (pinfunction "ADC1[8]-_PB06_9") (pintype "passive"))
    )
    (net (code "28") (name "/IN_13") (class "Default")
      (node (ref "C46") (pin "1") (pinfunction "1_1") (pintype "passive"))
      (node (ref "J8") (pin "1") (pinfunction "1_1") (pintype "passive"))
      (node (ref "R39") (pin "1") (pinfunction "1_1") (pintype "passive"))
      (node (ref "U13") (pin "6") (pinfunction "ADC1[7]_-_PB05_6") (pintype "passive"))
    )
    (net (code "29") (name "/IN_14") (class "Default")
      (node (ref "C45") (pin "1") (pinfunction "1_1") (pintype "passive"))
      (node (ref "J8") (pin "2") (pinfunction "2_2") (pintype "passive"))
      (node (ref "R41") (pin "1") (pinfunction "1_1") (pintype "passive"))
      (node (ref "U13") (pin "5") (pinfunction "ADC1[6]_-_PB04_5") (pintype "passive"))
    )
    (net (code "30") (name "/IN_15") (class "Default")
      (node (ref "C44") (pin "1") (pinfunction "1_1") (pintype "passive"))
      (node (ref "J8") (pin "3") (pinfunction "3_3") (pintype "passive"))
      (node (ref "R42") (pin "1") (pinfunction "1_1") (pintype "passive"))
      (node (ref "U13") (pin "4") (pinfunction "VREFA/ADC0[1]_-_PA03_4") (pintype "passive"))
    )
    (net (code "31") (name "/LED_DAT") (class "Default")
      (node (ref "R47") (pin "2") (pinfunction "2_2") (pintype "passive"))
      (node (ref "U5") (pin "4") (pinfunction "DIN_4") (pintype "input"))
    )
    (net (code "32") (name "/LED_D_OUT") (class "Default")
      (node (ref "R47") (pin "1") (pinfunction "1_1") (pintype "passive"))
      (node (ref "U13") (pin "49") (pinfunction "XIN1/PB22_49") (pintype "passive"))
    )
    (net (code "33") (name "/MISO") (class "Default")
      (node (ref "TFT1") (pin "33") (pinfunction "SDO_33") (pintype "passive"))
      (node (ref "U13") (pin "31") (pinfunction "XIN0/COM2[2]_-_PA14_31") (pintype "passive"))
    )
    (net (code "34") (name "/MISO_1") (class "Default")
      (node (ref "U13") (pin "36") (pinfunction "COM1[1]_-_PA17_36") (pintype "passive"))
      (node (ref "U22") (pin "7") (pinfunction "MISO_7") (pintype "passive"))
    )
    (net (code "35") (name "/MOSI") (class "Default")
      (node (ref "TFT1") (pin "34") (pinfunction "SDI_34") (pintype "passive"))
      (node (ref "U13") (pin "29") (pinfunction "COM2[0]_-_PA12_29") (pintype "passive"))
    )
    (net (code "36") (name "/MOSI_1") (class "Default")
      (node (ref "U13") (pin "38") (pinfunction "COM1[3]_-_PA19_38") (pintype "passive"))
      (node (ref "U22") (pin "6") (pinfunction "MOSI_6") (pintype "passive"))
    )
    (net (code "37") (name "/NRF_CE") (class "Default")
      (node (ref "U13") (pin "37") (pinfunction "COM1[2]_-_PA18_37") (pintype "passive"))
      (node (ref "U22") (pin "3") (pinfunction "CE_3") (pintype "passive"))
    )
    (net (code "38") (name "/NRF_CS") (class "Default")
      (node (ref "U13") (pin "39") (pinfunction "COM5[0]_-_PB16_39") (pintype "passive"))
      (node (ref "U22") (pin "4") (pinfunction "CSN_4") (pintype "passive"))
    )
    (net (code "39") (name "/NRF_IRQ") (class "Default")
      (node (ref "U13") (pin "40") (pinfunction "COM5[1]_-_PB17_40") (pintype "passive"))
      (node (ref "U22") (pin "8") (pinfunction "IRQ_8") (pintype "passive"))
    )
    (net (code "40") (name "/OUT_1") (class "Default")
      (node (ref "J9") (pin "1") (pinfunction "1_1") (pintype "passive"))
      (node (ref "Q1") (pin "D") (pinfunction "D_D") (pintype "passive"))
      (node (ref "TR1") (pin "2") (pinfunction "K_2") (pintype "passive"))
    )
    (net (code "41") (name "/OUT_2") (class "Default")
      (node (ref "J9") (pin "2") (pinfunction "2_2") (pintype "passive"))
      (node (ref "Q3") (pin "D") (pinfunction "D_D") (pintype "passive"))
      (node (ref "TR2") (pin "2") (pinfunction "K_2") (pintype "passive"))
    )
    (net (code "42") (name "/OUT_3") (class "Default")
      (node (ref "J9") (pin "3") (pinfunction "3_3") (pintype "passive"))
      (node (ref "Q6") (pin "D") (pinfunction "D_D") (pintype "passive"))
      (node (ref "TR3") (pin "2") (pinfunction "K_2") (pintype "passive"))
    )
    (net (code "43") (name "/RESET") (class "Default")
      (node (ref "C10") (pin "2") (pinfunction "2_2") (pintype "passive"))
      (node (ref "R5") (pin "1") (pinfunction "1_1") (pintype "passive"))
      (node (ref "SW1") (pin "1") (pinfunction "*_1") (pintype "passive"))
      (node (ref "SWD1") (pin "10") (pinfunction "10_10") (pintype "passive"))
      (node (ref "U13") (pin "52") (pinfunction "RESETN_52") (pintype "passive"))
    )
    (net (code "44") (name "/RTC_EI") (class "Default")
      (node (ref "R7") (pin "1") (pinfunction "1_1") (pintype "passive"))
      (node (ref "U2") (pin "7") (pinfunction "MFP_7") (pintype "passive"))
    )
    (net (code "45") (name "/SCK") (class "Default")
      (node (ref "TFT1") (pin "37") (pinfunction "RS_SCL_37") (pintype "passive"))
      (node (ref "U13") (pin "30") (pinfunction "COM2[1]_-_PA13_30") (pintype "passive"))
    )
    (net (code "46") (name "/SCK_1") (class "Default")
      (node (ref "U13") (pin "35") (pinfunction "COM1[0]_-_PA16_35") (pintype "passive"))
      (node (ref "U22") (pin "5") (pinfunction "SCK_5") (pintype "passive"))
    )
    (net (code "47") (name "/SCL") (class "Default")
      (node (ref "R26") (pin "1") (pinfunction "1_1") (pintype "passive"))
      (node (ref "TFT1") (pin "44") (pinfunction "TP_SCK_44") (pintype "passive"))
      (node (ref "U13") (pin "18") (pinfunction "ADC0[9]/ADC1[3]/COM0[1]_-_PA09_18") (pintype "passive"))
      (node (ref "U2") (pin "6") (pinfunction "SCL_6") (pintype "passive"))
    )
    (net (code "48") (name "/SDA") (class "Default")
      (node (ref "R25") (pin "1") (pinfunction "1_1") (pintype "passive"))
      (node (ref "TFT1") (pin "45") (pinfunction "TP_SDA_45") (pintype "passive"))
      (node (ref "U13") (pin "17") (pinfunction "ADC0[8]/ADC1[2]/COM0[0]_-_PA08_17") (pintype "passive"))
      (node (ref "U2") (pin "5") (pinfunction "SDA_5") (pintype "passive"))
    )
    (net (code "49") (name "/START") (class "Default")
      (node (ref "C18") (pin "1") (pinfunction "1_1") (pintype "passive"))
      (node (ref "J2") (pin "1") (pinfunction "1_1") (pintype "passive"))
      (node (ref "R9") (pin "1") (pinfunction "1_1") (pintype "passive"))
      (node (ref "U13") (pin "23") (pinfunction "PB10_23") (pintype "passive"))
    )
    (net (code "50") (name "/SWCLK") (class "Default")
      (node (ref "R6") (pin "1") (pinfunction "1_1") (pintype "passive"))
      (node (ref "SWD1") (pin "4") (pinfunction "4_4") (pintype "passive"))
      (node (ref "U13") (pin "57") (pinfunction "SWCLK_-_PA30_57") (pintype "passive"))
    )
    (net (code "51") (name "/SWDIO") (class "Default")
      (node (ref "SWD1") (pin "2") (pinfunction "2_2") (pintype "passive"))
      (node (ref "U13") (pin "58") (pinfunction "SWDIO_-_PA31_58") (pintype "passive"))
    )
    (net (code "52") (name "/TFT_CS") (class "Default")
      (node (ref "TFT1") (pin "38") (pinfunction "~{CS}_38") (pintype "passive"))
      (node (ref "U13") (pin "27") (pinfunction "COM4[2]_-_PB14_27") (pintype "passive"))
    )
    (net (code "53") (name "/TFT_DC") (class "Default")
      (node (ref "TFT1") (pin "36") (pinfunction "~{WR_RS}_36") (pintype "passive"))
      (node (ref "U13") (pin "32") (pinfunction "XOUT0/COM2[3]_-_PA15_32") (pintype "passive"))
    )
    (net (code "54") (name "/TFT_LED_PWM") (class "Default")
      (node (ref "R38") (pin "1") (pinfunction "1_1") (pintype "passive"))
      (node (ref "U13") (pin "28") (pinfunction "COM4[3]_-_PB15_28") (pintype "passive"))
    )
    (net (code "55") (name "/TFT_RST") (class "Default")
      (node (ref "TFT1") (pin "10") (pinfunction "~{RESET}_10") (pintype "passive"))
      (node (ref "TFT1") (pin "47") (pinfunction "~{TP_RES}_47") (pintype "passive"))
      (node (ref "U13") (pin "19") (pinfunction "ADC0[10]/COM0[2]_-_PA10_19") (pintype "passive"))
    )
    (net (code "56") (name "/TFT_T_IRQ") (class "Default")
      (node (ref "TFT1") (pin "46") (pinfunction "TP_IRQ_46") (pintype "passive"))
      (node (ref "U13") (pin "20") (pinfunction "ADC0[11]/COM0[3]_-_PA11_20") (pintype "passive"))
    )
    (net (code "57") (name "/USB_D_N") (class "Default")
      (node (ref "U13") (pin "45") (pinfunction "COM3[2]_-_PA24_45") (pintype "passive"))
      (node (ref "U4") (pin "3") (pinfunction "I/O_2_3") (pintype "power_in"))
      (node (ref "USB1") (pin "A7") (pinfunction "D-_A7") (pintype "bidirectional"))
      (node (ref "USB1") (pin "B7") (pinfunction "D-_B7") (pintype "bidirectional"))
    )
    (net (code "58") (name "/USB_D_P") (class "Default")
      (node (ref "U13") (pin "46") (pinfunction "COM3[3]_-_PA25_46") (pintype "passive"))
      (node (ref "U4") (pin "1") (pinfunction "I/O_1_1") (pintype "power_in"))
      (node (ref "USB1") (pin "A6") (pinfunction "D+_A6") (pintype "bidirectional"))
      (node (ref "USB1") (pin "B6") (pinfunction "D+_B6") (pintype "bidirectional"))
    )
    (net (code "59") (name "D_GND") (class "Default")
      (node (ref "BT1") (pin "-") (pinfunction "-_-") (pintype "passive"))
      (node (ref "C10") (pin "1") (pinfunction "1_1") (pintype "passive"))
      (node (ref "C11") (pin "1") (pinfunction "1_1") (pintype "passive"))
      (node (ref "C12") (pin "1") (pinfunction "1_1") (pintype "passive"))
      (node (ref "C13") (pin "1") (pinfunction "1_1") (pintype "passive"))
      (node (ref "C14") (pin "1") (pinfunction "1_1") (pintype "passive"))
      (node (ref "C15") (pin "1") (pinfunction "1_1") (pintype "passive"))
      (node (ref "C16") (pin "1") (pinfunction "1_1") (pintype "passive"))
      (node (ref "C17") (pin "2") (pinfunction "2_2") (pintype "passive"))
      (node (ref "C18") (pin "2") (pinfunction "2_2") (pintype "passive"))
      (node (ref "C19") (pin "2") (pinfunction "2_2") (pintype "passive"))
      (node (ref "C2") (pin "1") (pinfunction "1_1") (pintype "passive"))
      (node (ref "C20") (pin "2") (pinfunction "2_2") (pintype "passive"))
      (node (ref "C21") (pin "2") (pinfunction "2_2") (pintype "passive"))
      (node (ref "C22") (pin "2") (pinfunction "2_2") (pintype "passive"))
      (node (ref "C23") (pin "2") (pinfunction "2_2") (pintype "passive"))
      (node (ref "C24") (pin "2") (pinfunction "2_2") (pintype "passive"))
      (node (ref "C25") (pin "2") (pinfunction "2_2") (pintype "passive"))
      (node (ref "C26") (pin "2") (pinfunction "2_2") (pintype "passive"))
      (node (ref "C27") (pin "2") (pinfunction "2_2") (pintype "passive"))
      (node (ref "C28") (pin "2") (pinfunction "2_2") (pintype "passive"))
      (node (ref "C29") (pin "2") (pinfunction "2_2") (pintype "passive"))
      (node (ref "C3") (pin "1") (pinfunction "1_1") (pintype "passive"))
      (node (ref "C30") (pin "2") (pinfunction "2_2") (pintype "passive"))
      (node (ref "C31") (pin "2") (pinfunction "2_2") (pintype "passive"))
      (node (ref "C32") (pin "2") (pinfunction "2_2") (pintype "passive"))
      (node (ref "C33") (pin "2") (pinfunction "2_2") (pintype "passive"))
      (node (ref "C34") (pin "2") (pinfunction "2_2") (pintype "passive"))
      (node (ref "C35") (pin "2") (pinfunction "2_2") (pintype "passive"))
      (node (ref "C36") (pin "2") (pinfunction "2_2") (pintype "passive"))
      (node (ref "C37") (pin "2") (pinfunction "2_2") (pintype "passive"))
      (node (ref "C38") (pin "2") (pinfunction "2_2") (pintype "passive"))
      (node (ref "C39") (pin "2") (pinfunction "2_2") (pintype "passive"))
      (node (ref "C4") (pin "1") (pinfunction "1_1") (pintype "passive"))
      (node (ref "C40") (pin "2") (pinfunction "2_2") (pintype "passive"))
      (node (ref "C41") (pin "2") (pinfunction "2_2") (pintype "passive"))
      (node (ref "C42") (pin "2") (pinfunction "2_2") (pintype "passive"))
      (node (ref "C43") (pin "2") (pinfunction "2_2") (pintype "passive"))
      (node (ref "C44") (pin "2") (pinfunction "2_2") (pintype "passive"))
      (node (ref "C45") (pin "2") (pinfunction "2_2") (pintype "passive"))
      (node (ref "C46") (pin "2") (pinfunction "2_2") (pintype "passive"))
      (node (ref "C47") (pin "2") (pinfunction "2_2") (pintype "passive"))
      (node (ref "C48") (pin "2") (pinfunction "2_2") (pintype "passive"))
      (node (ref "C49") (pin "1") (pinfunction "1_1") (pintype "passive"))
      (node (ref "C5") (pin "1") (pinfunction "1_1") (pintype "passive"))
      (node (ref "C50") (pin "1") (pinfunction "1_1") (pintype "passive"))
      (node (ref "C51") (pin "1") (pinfunction "1_1") (pintype "passive"))
      (node (ref "C52") (pin "1") (pinfunction "1_1") (pintype "passive"))
      (node (ref "C53") (pin "2") (pinfunction "2_2") (pintype "passive"))
      (node (ref "C6") (pin "1") (pinfunction "1_1") (pintype "passive"))
      (node (ref "C7") (pin "2") (pinfunction "2_2") (pintype "passive"))
      (node (ref "C8") (pin "2") (pinfunction "2_2") (pintype "passive"))
      (node (ref "C9") (pin "2") (pinfunction "2_2") (pintype "passive"))
      (node (ref "D2") (pin "1") (pinfunction "A_1") (pintype "passive"))
      (node (ref "J1") (pin "2") (pinfunction "-_2") (pintype "passive"))
      (node (ref "J2") (pin "3") (pinfunction "3_3") (pintype "passive"))
      (node (ref "J4") (pin "5") (pinfunction "5_5") (pintype "passive"))
      (node (ref "J5") (pin "5") (pinfunction "5_5") (pintype "passive"))
      (node (ref "J6") (pin "10") (pinfunction "10_10") (pintype "passive"))
      (node (ref "J7") (pin "5") (pinfunction "5_5") (pintype "passive"))
      (node (ref "J8") (pin "5") (pinfunction "5_5") (pintype "passive"))
      (node (ref "J9") (pin "4") (pinfunction "4_4") (pintype "passive"))
      (node (ref "Q2") (pin "3") (pinfunction "S_3") (pintype "passive"))
      (node (ref "Q4") (pin "3") (pinfunction "S_3") (pintype "passive"))
      (node (ref "Q5") (pin "3") (pinfunction "S_3") (pintype "passive"))
      (node (ref "Q7") (pin "3") (pinfunction "S_3") (pintype "passive"))
      (node (ref "R18") (pin "1") (pinfunction "1_1") (pintype "passive"))
      (node (ref "R2") (pin "1") (pinfunction "1_1") (pintype "passive"))
      (node (ref "R3") (pin "1") (pinfunction "1_1") (pintype "passive"))
      (node (ref "R36") (pin "1") (pinfunction "1_1") (pintype "passive"))
      (node (ref "R37") (pin "1") (pinfunction "1_1") (pintype "passive"))
      (node (ref "R4") (pin "2") (pinfunction "2_2") (pintype "passive"))
      (node (ref "R46") (pin "1") (pinfunction "1_1") (pintype "passive"))
      (node (ref "R8") (pin "1") (pinfunction "1_1") (pintype "passive"))
      (node (ref "SW1") (pin "2") (pinfunction "*_2") (pintype "passive"))
      (node (ref "SWD1") (pin "3") (pinfunction "3_3") (pintype "passive"))
      (node (ref "SWD1") (pin "5") (pinfunction "5_5") (pintype "passive"))
      (node (ref "TFT1") (pin "43") (pinfunction "GND_43") (pintype "passive"))
      (node (ref "TFT1") (pin "48") (pinfunction "GND_48") (pintype "passive"))
      (node (ref "TFT1") (pin "49") (pinfunction "GND_49") (pintype "passive"))
      (node (ref "TFT1") (pin "50") (pinfunction "GND_50") (pintype "passive"))
      (node (ref "TFT1") (pin "6") (pinfunction "IM0_6") (pintype "passive"))
      (node (ref "TR1") (pin "1") (pinfunction "A_1") (pintype "passive"))
      (node (ref "TR2") (pin "1") (pinfunction "A_1") (pintype "passive"))
      (node (ref "TR3") (pin "1") (pinfunction "A_1") (pintype "passive"))
      (node (ref "U1") (pin "2") (pinfunction "GND_2") (pintype "power_in"))
      (node (ref "U10") (pin "3") (pinfunction "VSS_3") (pintype "power_in"))
      (node (ref "U11") (pin "3") (pinfunction "VSS_3") (pintype "power_in"))
      (node (ref "U12") (pin "3") (pinfunction "VSS_3") (pintype "power_in"))
      (node (ref "U13") (pin "22") (pinfunction "GND_22") (pintype "passive"))
      (node (ref "U13") (pin "33") (pinfunction "GND_33") (pintype "passive"))
      (node (ref "U13") (pin "47") (pinfunction "GND_47") (pintype "passive"))
      (node (ref "U13") (pin "54") (pinfunction "GND_54") (pintype "passive"))
      (node (ref "U13") (pin "65") (pinfunction "PAD_65") (pintype "power_in"))
      (node (ref "U13") (pin "7") (pinfunction "GNDANA_7") (pintype "passive"))
      (node (ref "U14") (pin "3") (pinfunction "VSS_3") (pintype "power_in"))
      (node (ref "U15") (pin "3") (pinfunction "VSS_3") (pintype "power_in"))
      (node (ref "U16") (pin "3") (pinfunction "VSS_3") (pintype "power_in"))
      (node (ref "U17") (pin "3") (pinfunction "VSS_3") (pintype "power_in"))
      (node (ref "U18") (pin "3") (pinfunction "VSS_3") (pintype "power_in"))
      (node (ref "U19") (pin "3") (pinfunction "VSS_3") (pintype "power_in"))
      (node (ref "U2") (pin "4") (pinfunction "VSS_4") (pintype "passive"))
      (node (ref "U2") (pin "PAD") (pinfunction "PAD_PAD") (pintype "passive"))
      (node (ref "U20") (pin "3") (pinfunction "VSS_3") (pintype "power_in"))
      (node (ref "U21") (pin "3") (pinfunction "VSS_3") (pintype "power_in"))
      (node (ref "U22") (pin "1") (pinfunction "GND_1") (pintype "passive"))
      (node (ref "U3") (pin "4") (pinfunction "GND_4") (pintype "power_in"))
      (node (ref "U3") (pin "9") (pinfunction "PAD_9") (pintype "power_in"))
      (node (ref "U4") (pin "5") (pinfunction "GND_5") (pintype "power_in"))
      (node (ref "U5") (pin "3") (pinfunction "VSS_3") (pintype "power_in"))
      (node (ref "U6") (pin "3") (pinfunction "VSS_3") (pintype "power_in"))
      (node (ref "U7") (pin "3") (pinfunction "VSS_3") (pintype "power_in"))
      (node (ref "U8") (pin "3") (pinfunction "VSS_3") (pintype "power_in"))
      (node (ref "U9") (pin "3") (pinfunction "VSS_3") (pintype "power_in"))
      (node (ref "USB1") (pin "A1") (pinfunction "GND_A1") (pintype "power_in"))
      (node (ref "USB1") (pin "A12") (pinfunction "GND_A12") (pintype "power_in"))
      (node (ref "USB1") (pin "B1") (pinfunction "GND_B1") (pintype "power_in"))
      (node (ref "USB1") (pin "B12") (pinfunction "GND_B12") (pintype "power_in"))
    )
    (net (code "60") (name "Net-(C12-Pad2)") (class "Default")
      (node (ref "C12") (pin "2") (pinfunction "2_2") (pintype "passive"))
      (node (ref "C13") (pin "2") (pinfunction "2_2") (pintype "passive"))
      (node (ref "R8") (pin "2") (pinfunction "2_2") (pintype "passive"))
      (node (ref "USB1") (pin "EXT_SHLD") (pintype "passive"))
      (node (ref "USB1") (pin "INT_SHLD") (pintype "passive"))
    )
    (net (code "61") (name "Net-(D1-K)") (class "Default")
      (node (ref "C2") (pin "2") (pinfunction "2_2") (pintype "passive"))
      (node (ref "C3") (pin "2") (pinfunction "2_2") (pintype "passive"))
      (node (ref "C4") (pin "2") (pinfunction "2_2") (pintype "passive"))
      (node (ref "D1") (pin "2") (pinfunction "K_2") (pintype "passive"))
      (node (ref "U1") (pin "5") (pinfunction "VIN_5") (pintype "power_in"))
    )
    (net (code "62") (name "Net-(D2-K)") (class "Default")
      (node (ref "C1") (pin "2") (pinfunction "2_2") (pintype "passive"))
      (node (ref "D2") (pin "2") (pinfunction "K_2") (pintype "passive"))
      (node (ref "L1") (pin "1") (pinfunction "1_1") (pintype "passive"))
      (node (ref "U1") (pin "6") (pinfunction "SW_6") (pintype "output"))
    )
    (net (code "63") (name "Net-(J1-+)") (class "Default")
      (node (ref "F1") (pin "1") (pinfunction "1_1") (pintype "passive"))
      (node (ref "J1") (pin "1") (pinfunction "+_1") (pintype "passive"))
    )
    (net (code "64") (name "Net-(Q1-PadG)") (class "Default")
      (node (ref "Q1") (pin "G") (pinfunction "G_G") (pintype "passive"))
      (node (ref "R10") (pin "1") (pinfunction "1_1") (pintype "passive"))
      (node (ref "R12") (pin "2") (pinfunction "2_2") (pintype "passive"))
    )
    (net (code "65") (name "Net-(Q2-D)") (class "Default")
      (node (ref "Q2") (pin "2") (pinfunction "D_2") (pintype "passive"))
      (node (ref "R12") (pin "1") (pinfunction "1_1") (pintype "passive"))
    )
    (net (code "66") (name "Net-(Q2-G)") (class "Default")
      (node (ref "C25") (pin "1") (pinfunction "1_1") (pintype "passive"))
      (node (ref "Q2") (pin "1") (pinfunction "G_1") (pintype "passive"))
      (node (ref "R17") (pin "2") (pinfunction "2_2") (pintype "passive"))
      (node (ref "R18") (pin "2") (pinfunction "2_2") (pintype "passive"))
    )
    (net (code "67") (name "Net-(Q3-PadG)") (class "Default")
      (node (ref "Q3") (pin "G") (pinfunction "G_G") (pintype "passive"))
      (node (ref "R21") (pin "1") (pinfunction "1_1") (pintype "passive"))
      (node (ref "R24") (pin "2") (pinfunction "2_2") (pintype "passive"))
    )
    (net (code "68") (name "Net-(Q4-D)") (class "Default")
      (node (ref "Q4") (pin "2") (pinfunction "D_2") (pintype "passive"))
      (node (ref "R24") (pin "1") (pinfunction "1_1") (pintype "passive"))
    )
    (net (code "69") (name "Net-(Q4-G)") (class "Default")
      (node (ref "C36") (pin "1") (pinfunction "1_1") (pintype "passive"))
      (node (ref "Q4") (pin "1") (pinfunction "G_1") (pintype "passive"))
      (node (ref "R34") (pin "2") (pinfunction "2_2") (pintype "passive"))
      (node (ref "R36") (pin "2") (pinfunction "2_2") (pintype "passive"))
    )
    (net (code "70") (name "Net-(Q5-D)") (class "Default")
      (node (ref "Q5") (pin "2") (pinfunction "D_2") (pintype "passive"))
      (node (ref "TFT1") (pin "1") (pinfunction "LEDK_1") (pintype "passive"))
    )
    (net (code "71") (name "Net-(Q5-G)") (class "Default")
      (node (ref "Q5") (pin "1") (pinfunction "G_1") (pintype "passive"))
      (node (ref "R37") (pin "2") (pinfunction "2_2") (pintype "passive"))
      (node (ref "R38") (pin "2") (pinfunction "2_2") (pintype "passive"))
    )
    (net (code "72") (name "Net-(Q6-PadG)") (class "Default")
      (node (ref "Q6") (pin "G") (pinfunction "G_G") (pintype "passive"))
      (node (ref "R40") (pin "1") (pinfunction "1_1") (pintype "passive"))
      (node (ref "R44") (pin "2") (pinfunction "2_2") (pintype "passive"))
    )
    (net (code "73") (name "Net-(Q7-D)") (class "Default")
      (node (ref "Q7") (pin "2") (pinfunction "D_2") (pintype "passive"))
      (node (ref "R44") (pin "1") (pinfunction "1_1") (pintype "passive"))
    )
    (net (code "74") (name "Net-(Q7-G)") (class "Default")
      (node (ref "C48") (pin "1") (pinfunction "1_1") (pintype "passive"))
      (node (ref "Q7") (pin "1") (pinfunction "G_1") (pintype "passive"))
      (node (ref "R45") (pin "2") (pinfunction "2_2") (pintype "passive"))
      (node (ref "R46") (pin "2") (pinfunction "2_2") (pintype "passive"))
    )
    (net (code "75") (name "Net-(TFT1-DB0)") (class "Default")
      (node (ref "TFT1") (pin "15") (pinfunction "DB17_15") (pintype "passive"))
      (node (ref "TFT1") (pin "16") (pinfunction "DB16_16") (pintype "passive"))
      (node (ref "TFT1") (pin "17") (pinfunction "DB15_17") (pintype "passive"))
      (node (ref "TFT1") (pin "18") (pinfunction "DB14_18") (pintype "passive"))
      (node (ref "TFT1") (pin "19") (pinfunction "DB13_19") (pintype "passive"))
      (node (ref "TFT1") (pin "20") (pinfunction "DB12_20") (pintype "passive"))
      (node (ref "TFT1") (pin "21") (pinfunction "DB11_21") (pintype "passive"))
      (node (ref "TFT1") (pin "22") (pinfunction "DB10_22") (pintype "passive"))
      (node (ref "TFT1") (pin "23") (pinfunction "DB9_23") (pintype "passive"))
      (node (ref "TFT1") (pin "24") (pinfunction "DB8_24") (pintype "passive"))
      (node (ref "TFT1") (pin "25") (pinfunction "DB7_25") (pintype "passive"))
      (node (ref "TFT1") (pin "26") (pinfunction "DB6_26") (pintype "passive"))
      (node (ref "TFT1") (pin "27") (pinfunction "DB5_27") (pintype "passive"))
      (node (ref "TFT1") (pin "28") (pinfunction "DB4_28") (pintype "passive"))
      (node (ref "TFT1") (pin "29") (pinfunction "DB3_29") (pintype "passive"))
      (node (ref "TFT1") (pin "30") (pinfunction "DB2_30") (pintype "passive"))
      (node (ref "TFT1") (pin "31") (pinfunction "DB1_31") (pintype "passive"))
      (node (ref "TFT1") (pin "32") (pinfunction "DB0_32") (pintype "passive"))
    )
    (net (code "76") (name "Net-(TFT1-LEDA1)") (class "Default")
      (node (ref "R27") (pin "1") (pinfunction "1_1") (pintype "passive"))
      (node (ref "TFT1") (pin "2") (pinfunction "LEDA1_2") (pintype "passive"))
    )
    (net (code "77") (name "Net-(TFT1-LEDA2)") (class "Default")
      (node (ref "R28") (pin "1") (pinfunction "1_1") (pintype "passive"))
      (node (ref "TFT1") (pin "3") (pinfunction "LEDA2_3") (pintype "passive"))
    )
    (net (code "78") (name "Net-(TFT1-LEDA3)") (class "Default")
      (node (ref "R30") (pin "1") (pinfunction "1_1") (pintype "passive"))
      (node (ref "TFT1") (pin "4") (pinfunction "LEDA3_4") (pintype "passive"))
    )
    (net (code "79") (name "Net-(TFT1-LEDA4)") (class "Default")
      (node (ref "R32") (pin "1") (pinfunction "1_1") (pintype "passive"))
      (node (ref "TFT1") (pin "5") (pinfunction "LEDA4_5") (pintype "passive"))
    )
    (net (code "80") (name "Net-(U1-CB)") (class "Default")
      (node (ref "C1") (pin "1") (pinfunction "1_1") (pintype "passive"))
      (node (ref "U1") (pin "1") (pinfunction "CB_1") (pintype "input"))
    )
    (net (code "81") (name "Net-(U1-FB)") (class "Default")
      (node (ref "R1") (pin "2") (pinfunction "2_2") (pintype "passive"))
      (node (ref "R2") (pin "2") (pinfunction "2_2") (pintype "passive"))
      (node (ref "U1") (pin "3") (pinfunction "FB_3") (pintype "input"))
    )
    (net (code "82") (name "Net-(U2-VBAT)") (class "Default")
      (node (ref "BT1") (pin "+") (pinfunction "+_+") (pintype "passive"))
      (node (ref "U2") (pin "3") (pinfunction "VBAT_3") (pintype "passive"))
    )
    (net (code "83") (name "Net-(U2-X1)") (class "Default")
      (node (ref "C8") (pin "1") (pinfunction "1_1") (pintype "passive"))
      (node (ref "U2") (pin "1") (pinfunction "X1_1") (pintype "passive"))
      (node (ref "X1") (pin "2") (pinfunction "OSC2_2") (pintype "passive"))
    )
    (net (code "84") (name "Net-(U2-X2)") (class "Default")
      (node (ref "C7") (pin "1") (pinfunction "1_1") (pintype "passive"))
      (node (ref "U2") (pin "2") (pinfunction "X2_2") (pintype "passive"))
      (node (ref "X1") (pin "1") (pinfunction "OSC1_1") (pintype "passive"))
    )
    (net (code "85") (name "Net-(U5-DOUT)") (class "Default")
      (node (ref "U5") (pin "2") (pinfunction "DOUT_2") (pintype "output"))
      (node (ref "U6") (pin "4") (pinfunction "DIN_4") (pintype "input"))
    )
    (net (code "86") (name "Net-(U6-DOUT)") (class "Default")
      (node (ref "U6") (pin "2") (pinfunction "DOUT_2") (pintype "output"))
      (node (ref "U7") (pin "4") (pinfunction "DIN_4") (pintype "input"))
    )
    (net (code "87") (name "Net-(U7-DOUT)") (class "Default")
      (node (ref "U7") (pin "2") (pinfunction "DOUT_2") (pintype "output"))
      (node (ref "U8") (pin "4") (pinfunction "DIN_4") (pintype "input"))
    )
    (net (code "88") (name "Net-(U8-DOUT)") (class "Default")
      (node (ref "U8") (pin "2") (pinfunction "DOUT_2") (pintype "output"))
      (node (ref "U9") (pin "4") (pinfunction "DIN_4") (pintype "input"))
    )
    (net (code "89") (name "Net-(U10-DIN)") (class "Default")
      (node (ref "U10") (pin "4") (pinfunction "DIN_4") (pintype "input"))
      (node (ref "U9") (pin "2") (pinfunction "DOUT_2") (pintype "output"))
    )
    (net (code "90") (name "Net-(U10-DOUT)") (class "Default")
      (node (ref "U10") (pin "2") (pinfunction "DOUT_2") (pintype "output"))
      (node (ref "U11") (pin "4") (pinfunction "DIN_4") (pintype "input"))
    )
    (net (code "91") (name "Net-(U11-DOUT)") (class "Default")
      (node (ref "U11") (pin "2") (pinfunction "DOUT_2") (pintype "output"))
      (node (ref "U12") (pin "4") (pinfunction "DIN_4") (pintype "input"))
    )
    (net (code "92") (name "Net-(U12-DOUT)") (class "Default")
      (node (ref "U12") (pin "2") (pinfunction "DOUT_2") (pintype "output"))
      (node (ref "U14") (pin "4") (pinfunction "DIN_4") (pintype "input"))
    )
    (net (code "93") (name "Net-(U13-VDDANA)") (class "Default")
      (node (ref "C41") (pin "1") (pinfunction "1_1") (pintype "passive"))
      (node (ref "C42") (pin "1") (pinfunction "1_1") (pintype "passive"))
      (node (ref "L3") (pin "2") (pinfunction "2_2") (pintype "passive"))
      (node (ref "U13") (pin "8") (pinfunction "VDDANA_8") (pintype "passive"))
    )
    (net (code "94") (name "Net-(U13-VDDCORE)") (class "Default")
      (node (ref "C34") (pin "1") (pinfunction "1_1") (pintype "passive"))
      (node (ref "C35") (pin "1") (pinfunction "1_1") (pintype "passive"))
      (node (ref "U13") (pin "53") (pinfunction "VDDCORE_53") (pintype "power_in"))
    )
    (net (code "95") (name "Net-(U13-VDDIOB)") (class "Default")
      (node (ref "C20") (pin "1") (pinfunction "1_1") (pintype "passive"))
      (node (ref "C26") (pin "1") (pinfunction "1_1") (pintype "passive"))
      (node (ref "C27") (pin "1") (pinfunction "1_1") (pintype "passive"))
      (node (ref "C28") (pin "1") (pinfunction "1_1") (pintype "passive"))
      (node (ref "C29") (pin "1") (pinfunction "1_1") (pintype "passive"))
      (node (ref "L2") (pin "2") (pinfunction "2_2") (pintype "passive"))
      (node (ref "U13") (pin "21") (pinfunction "VDDIOB_21") (pintype "passive"))
      (node (ref "U13") (pin "34") (pinfunction "VDDIO_34") (pintype "passive"))
      (node (ref "U13") (pin "48") (pinfunction "VDDIO_48") (pintype "passive"))
      (node (ref "U13") (pin "56") (pinfunction "VDDIO_56") (pintype "passive"))
    )
    (net (code "96") (name "Net-(U13-XIN32_-_PA00)") (class "Default")
      (node (ref "C15") (pin "2") (pinfunction "2_2") (pintype "passive"))
      (node (ref "U13") (pin "1") (pinfunction "XIN32_-_PA00_1") (pintype "passive"))
      (node (ref "X2") (pin "1") (pinfunction "OSC1_1") (pintype "passive"))
    )
    (net (code "97") (name "Net-(U13-XOUT32_-_PA01)") (class "Default")
      (node (ref "C16") (pin "2") (pinfunction "2_2") (pintype "passive"))
      (node (ref "U13") (pin "2") (pinfunction "XOUT32_-_PA01_2") (pintype "passive"))
      (node (ref "X2") (pin "2") (pinfunction "OSC2_2") (pintype "passive"))
    )
    (net (code "98") (name "Net-(U14-DOUT)") (class "Default")
      (node (ref "U14") (pin "2") (pinfunction "DOUT_2") (pintype "output"))
      (node (ref "U15") (pin "4") (pinfunction "DIN_4") (pintype "input"))
    )
    (net (code "99") (name "Net-(U15-DOUT)") (class "Default")
      (node (ref "U15") (pin "2") (pinfunction "DOUT_2") (pintype "output"))
      (node (ref "U16") (pin "4") (pinfunction "DIN_4") (pintype "input"))
    )
    (net (code "100") (name "Net-(U16-DOUT)") (class "Default")
      (node (ref "U16") (pin "2") (pinfunction "DOUT_2") (pintype "output"))
      (node (ref "U17") (pin "4") (pinfunction "DIN_4") (pintype "input"))
    )
    (net (code "101") (name "Net-(U17-DOUT)") (class "Default")
      (node (ref "U17") (pin "2") (pinfunction "DOUT_2") (pintype "output"))
      (node (ref "U18") (pin "4") (pinfunction "DIN_4") (pintype "input"))
    )
    (net (code "102") (name "Net-(U18-DOUT)") (class "Default")
      (node (ref "U18") (pin "2") (pinfunction "DOUT_2") (pintype "output"))
      (node (ref "U19") (pin "4") (pinfunction "DIN_4") (pintype "input"))
    )
    (net (code "103") (name "Net-(U19-DOUT)") (class "Default")
      (node (ref "U19") (pin "2") (pinfunction "DOUT_2") (pintype "output"))
      (node (ref "U20") (pin "4") (pinfunction "DIN_4") (pintype "input"))
    )
    (net (code "104") (name "Net-(U20-DOUT)") (class "Default")
      (node (ref "U20") (pin "2") (pinfunction "DOUT_2") (pintype "output"))
      (node (ref "U21") (pin "4") (pinfunction "DIN_4") (pintype "input"))
    )
    (net (code "105") (name "Net-(USB1-CC1)") (class "Default")
      (node (ref "R4") (pin "1") (pinfunction "1_1") (pintype "passive"))
      (node (ref "USB1") (pin "A5") (pinfunction "CC1_A5") (pintype "passive"))
    )
    (net (code "106") (name "Net-(USB1-CC2)") (class "Default")
      (node (ref "R3") (pin "2") (pinfunction "2_2") (pintype "passive"))
      (node (ref "USB1") (pin "B5") (pinfunction "CC2_B5") (pintype "passive"))
    )
    (net (code "107") (name "Vbus") (class "Default")
      (node (ref "D3") (pin "1") (pinfunction "A_1") (pintype "passive"))
      (node (ref "USB1") (pin "A4") (pinfunction "Vbus_A4") (pintype "power_in"))
      (node (ref "USB1") (pin "A9") (pinfunction "Vbus_A9") (pintype "power_in"))
      (node (ref "USB1") (pin "B4") (pinfunction "Vbus_B4") (pintype "power_in"))
      (node (ref "USB1") (pin "B9") (pinfunction "Vbus_B9") (pintype "power_in"))
    )
    (net (code "108") (name "unconnected-(SWD1-Pad6)") (class "Default")
      (node (ref "SWD1") (pin "6") (pinfunction "6_6") (pintype "passive"))
    )
    (net (code "109") (name "unconnected-(SWD1-Pad7)") (class "Default")
      (node (ref "SWD1") (pin "7") (pinfunction "7_7") (pintype "passive"))
    )
    (net (code "110") (name "unconnected-(SWD1-Pad8)") (class "Default")
      (node (ref "SWD1") (pin "8") (pinfunction "8_8") (pintype "passive"))
    )
    (net (code "111") (name "unconnected-(SWD1-Pad9)") (class "Default")
      (node (ref "SWD1") (pin "9") (pinfunction "9_9") (pintype "passive"))
    )
    (net (code "112") (name "unconnected-(TFT1-DE-Pad14)") (class "Default")
      (node (ref "TFT1") (pin "14") (pinfunction "DE_14") (pintype "passive"))
    )
    (net (code "113") (name "unconnected-(TFT1-DOTCLK-Pad13)") (class "Default")
      (node (ref "TFT1") (pin "13") (pinfunction "DOTCLK_13") (pintype "passive"))
    )
    (net (code "114") (name "unconnected-(TFT1-HSYNC-Pad12)") (class "Default")
      (node (ref "TFT1") (pin "12") (pinfunction "HSYNC_12") (pintype "passive"))
    )
    (net (code "115") (name "unconnected-(TFT1-TE-Pad39)") (class "Default")
      (node (ref "TFT1") (pin "39") (pinfunction "TE_39") (pintype "passive"))
    )
    (net (code "116") (name "unconnected-(TFT1-VSYNC-Pad11)") (class "Default")
      (node (ref "TFT1") (pin "11") (pinfunction "VSYNC_11") (pintype "passive"))
    )
    (net (code "117") (name "unconnected-(TFT1-~{RD}-Pad35)") (class "Default")
      (node (ref "TFT1") (pin "35") (pinfunction "~{RD}_35") (pintype "passive"))
    )
    (net (code "118") (name "unconnected-(U1-~{SHDN}-Pad4)") (class "Default")
      (node (ref "U1") (pin "4") (pinfunction "~{SHDN}_4") (pintype "input"))
    )
    (net (code "119") (name "unconnected-(U3-NC-Pad2)") (class "Default")
      (node (ref "U3") (pin "2") (pinfunction "NC_2") (pintype "passive"))
    )
    (net (code "120") (name "unconnected-(U3-NC-Pad3)") (class "Default")
      (node (ref "U3") (pin "3") (pinfunction "NC_3") (pintype "passive"))
    )
    (net (code "121") (name "unconnected-(U3-NC-Pad5)") (class "Default")
      (node (ref "U3") (pin "5") (pinfunction "NC_5") (pintype "passive"))
    )
    (net (code "122") (name "unconnected-(U3-NC-Pad6)") (class "Default")
      (node (ref "U3") (pin "6") (pinfunction "NC_6") (pintype "passive"))
    )
    (net (code "123") (name "unconnected-(U3-NC-Pad7)") (class "Default")
      (node (ref "U3") (pin "7") (pinfunction "NC_7") (pintype "passive"))
    )
    (net (code "124") (name "unconnected-(U4-I{slash}O_3-Pad4)") (class "Default")
      (node (ref "U4") (pin "4") (pinfunction "I/O_3_4") (pintype "power_in"))
    )
    (net (code "125") (name "unconnected-(U4-I{slash}O_4-Pad6)") (class "Default")
      (node (ref "U4") (pin "6") (pinfunction "I/O_4_6") (pintype "power_in"))
    )
    (net (code "126") (name "unconnected-(U13-VSW-Pad55)") (class "Default")
      (node (ref "U13") (pin "55") (pinfunction "VSW_55") (pintype "passive"))
    )
    (net (code "127") (name "unconnected-(U21-DOUT-Pad2)") (class "Default")
      (node (ref "U21") (pin "2") (pinfunction "DOUT_2") (pintype "output"))
    )
    (net (code "128") (name "unconnected-(USB1-RX1+-PadB11)") (class "Default")
      (node (ref "USB1") (pin "B11") (pinfunction "RX1+_B11") (pintype "input"))
    )
    (net (code "129") (name "unconnected-(USB1-RX1--PadB10)") (class "Default")
      (node (ref "USB1") (pin "B10") (pinfunction "RX1-_B10") (pintype "input"))
    )
    (net (code "130") (name "unconnected-(USB1-RX2+-PadA11)") (class "Default")
      (node (ref "USB1") (pin "A11") (pinfunction "RX2+_A11") (pintype "input"))
    )
    (net (code "131") (name "unconnected-(USB1-RX2--PadA10)") (class "Default")
      (node (ref "USB1") (pin "A10") (pinfunction "RX2-_A10") (pintype "input"))
    )
    (net (code "132") (name "unconnected-(USB1-SBU1-PadA8)") (class "Default")
      (node (ref "USB1") (pin "A8") (pinfunction "SBU1_A8") (pintype "passive"))
    )
    (net (code "133") (name "unconnected-(USB1-SBU2-PadB8)") (class "Default")
      (node (ref "USB1") (pin "B8") (pinfunction "SBU2_B8") (pintype "passive"))
    )
    (net (code "134") (name "unconnected-(USB1-TX1+-PadA2)") (class "Default")
      (node (ref "USB1") (pin "A2") (pinfunction "TX1+_A2") (pintype "output"))
    )
    (net (code "135") (name "unconnected-(USB1-TX1--PadA3)") (class "Default")
      (node (ref "USB1") (pin "A3") (pinfunction "TX1-_A3") (pintype "output"))
    )
    (net (code "136") (name "unconnected-(USB1-TX2+-PadB2)") (class "Default")
      (node (ref "USB1") (pin "B2") (pinfunction "TX2+_B2") (pintype "output"))
    )
    (net (code "137") (name "unconnected-(USB1-TX2--PadB3)") (class "Default")
      (node (ref "USB1") (pin "B3") (pinfunction "TX2-_B3") (pintype "output"))
    )
  )
)
